# axiom_beta_interface_dummy_v0_13_r1_3.net
KiCad netlist of a schematic drawn in EAGLE
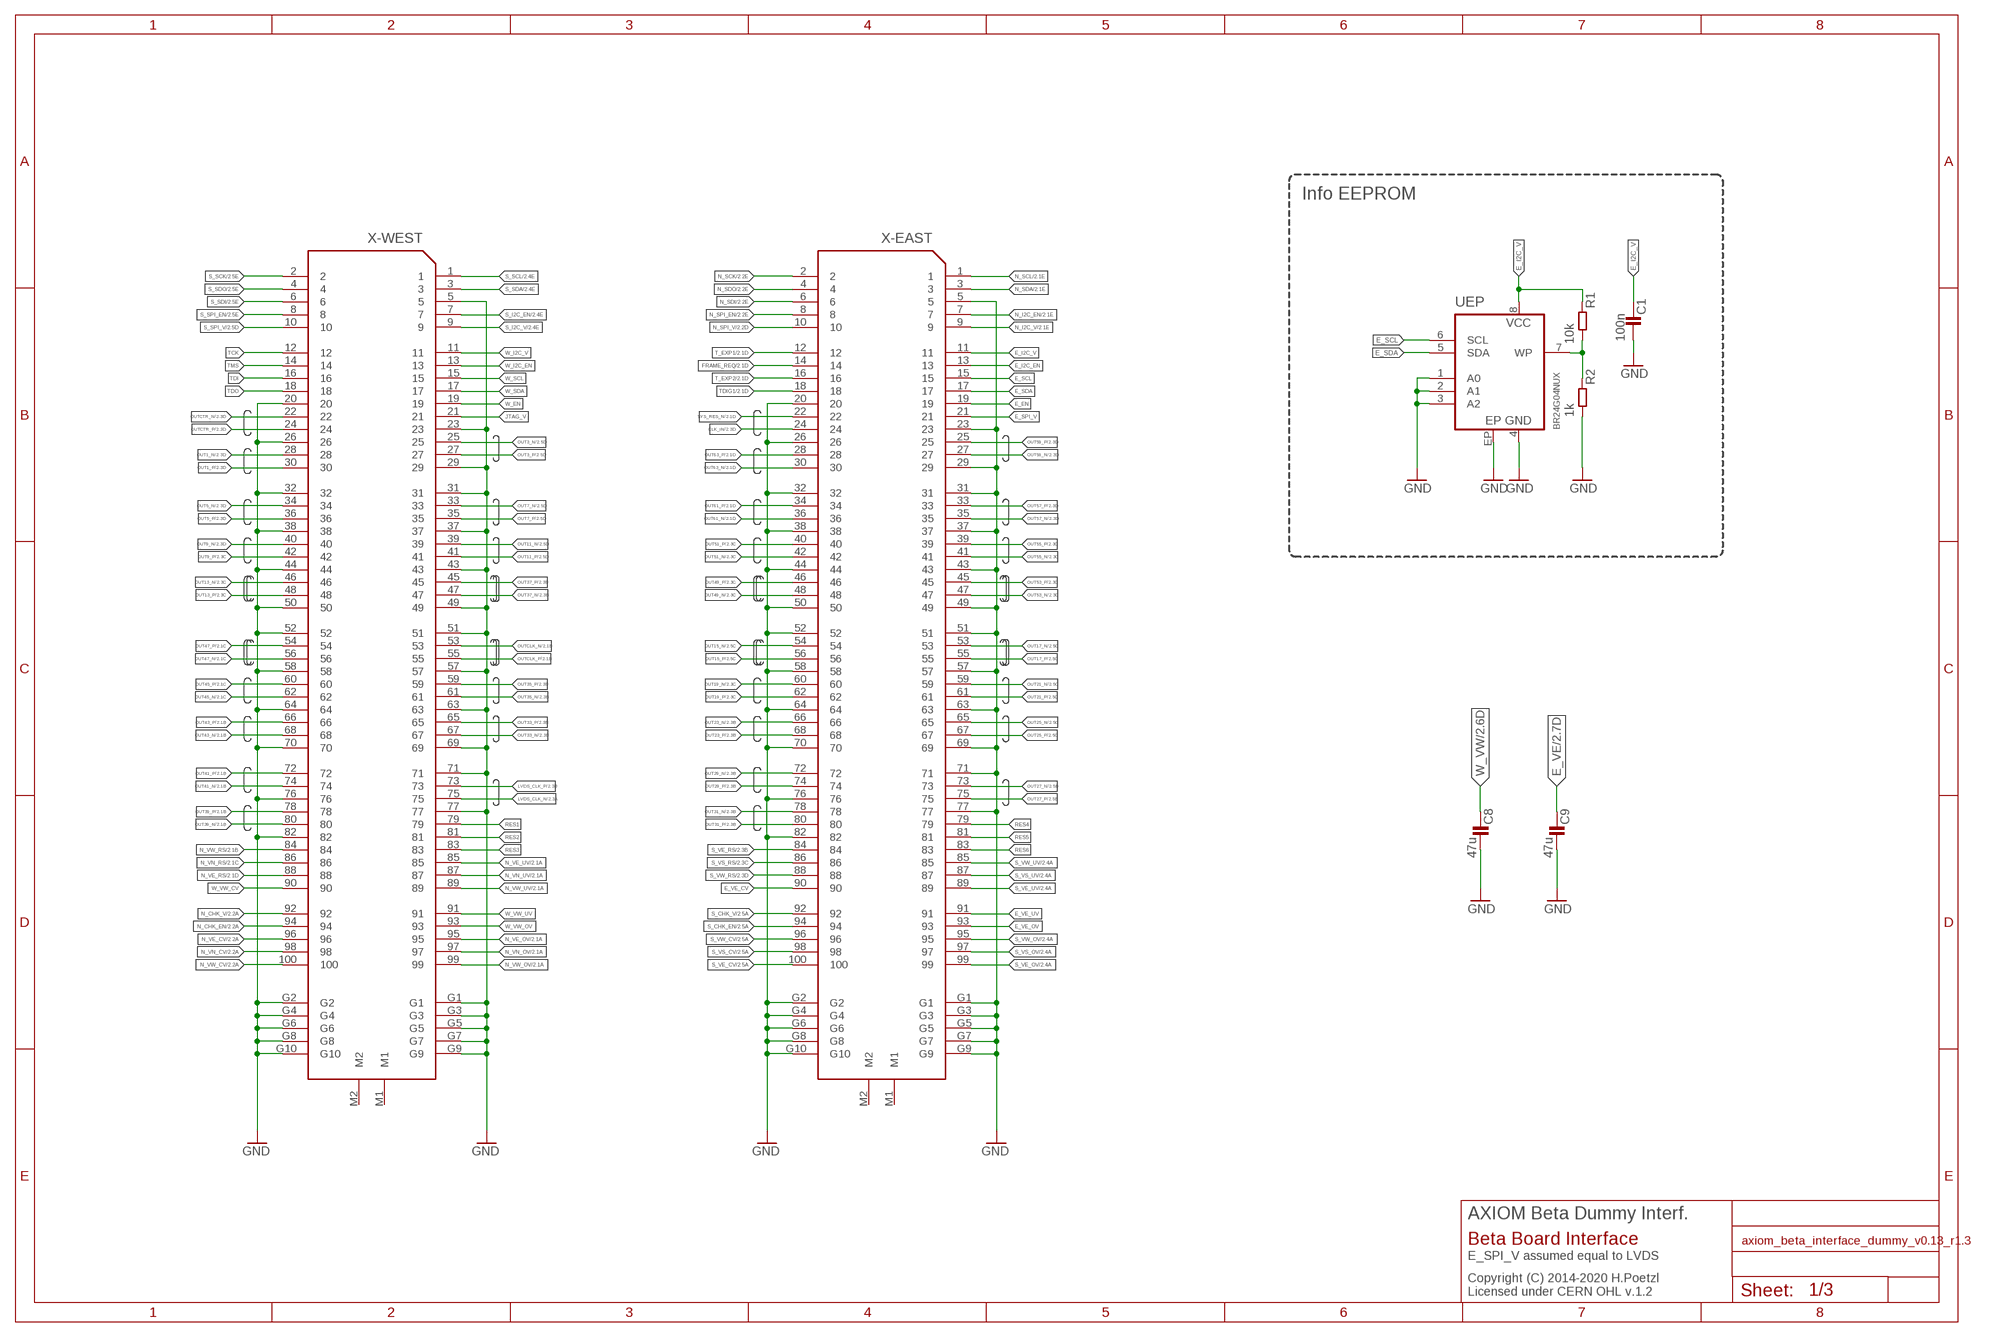
[diagram p0: schematic, sheet 1]
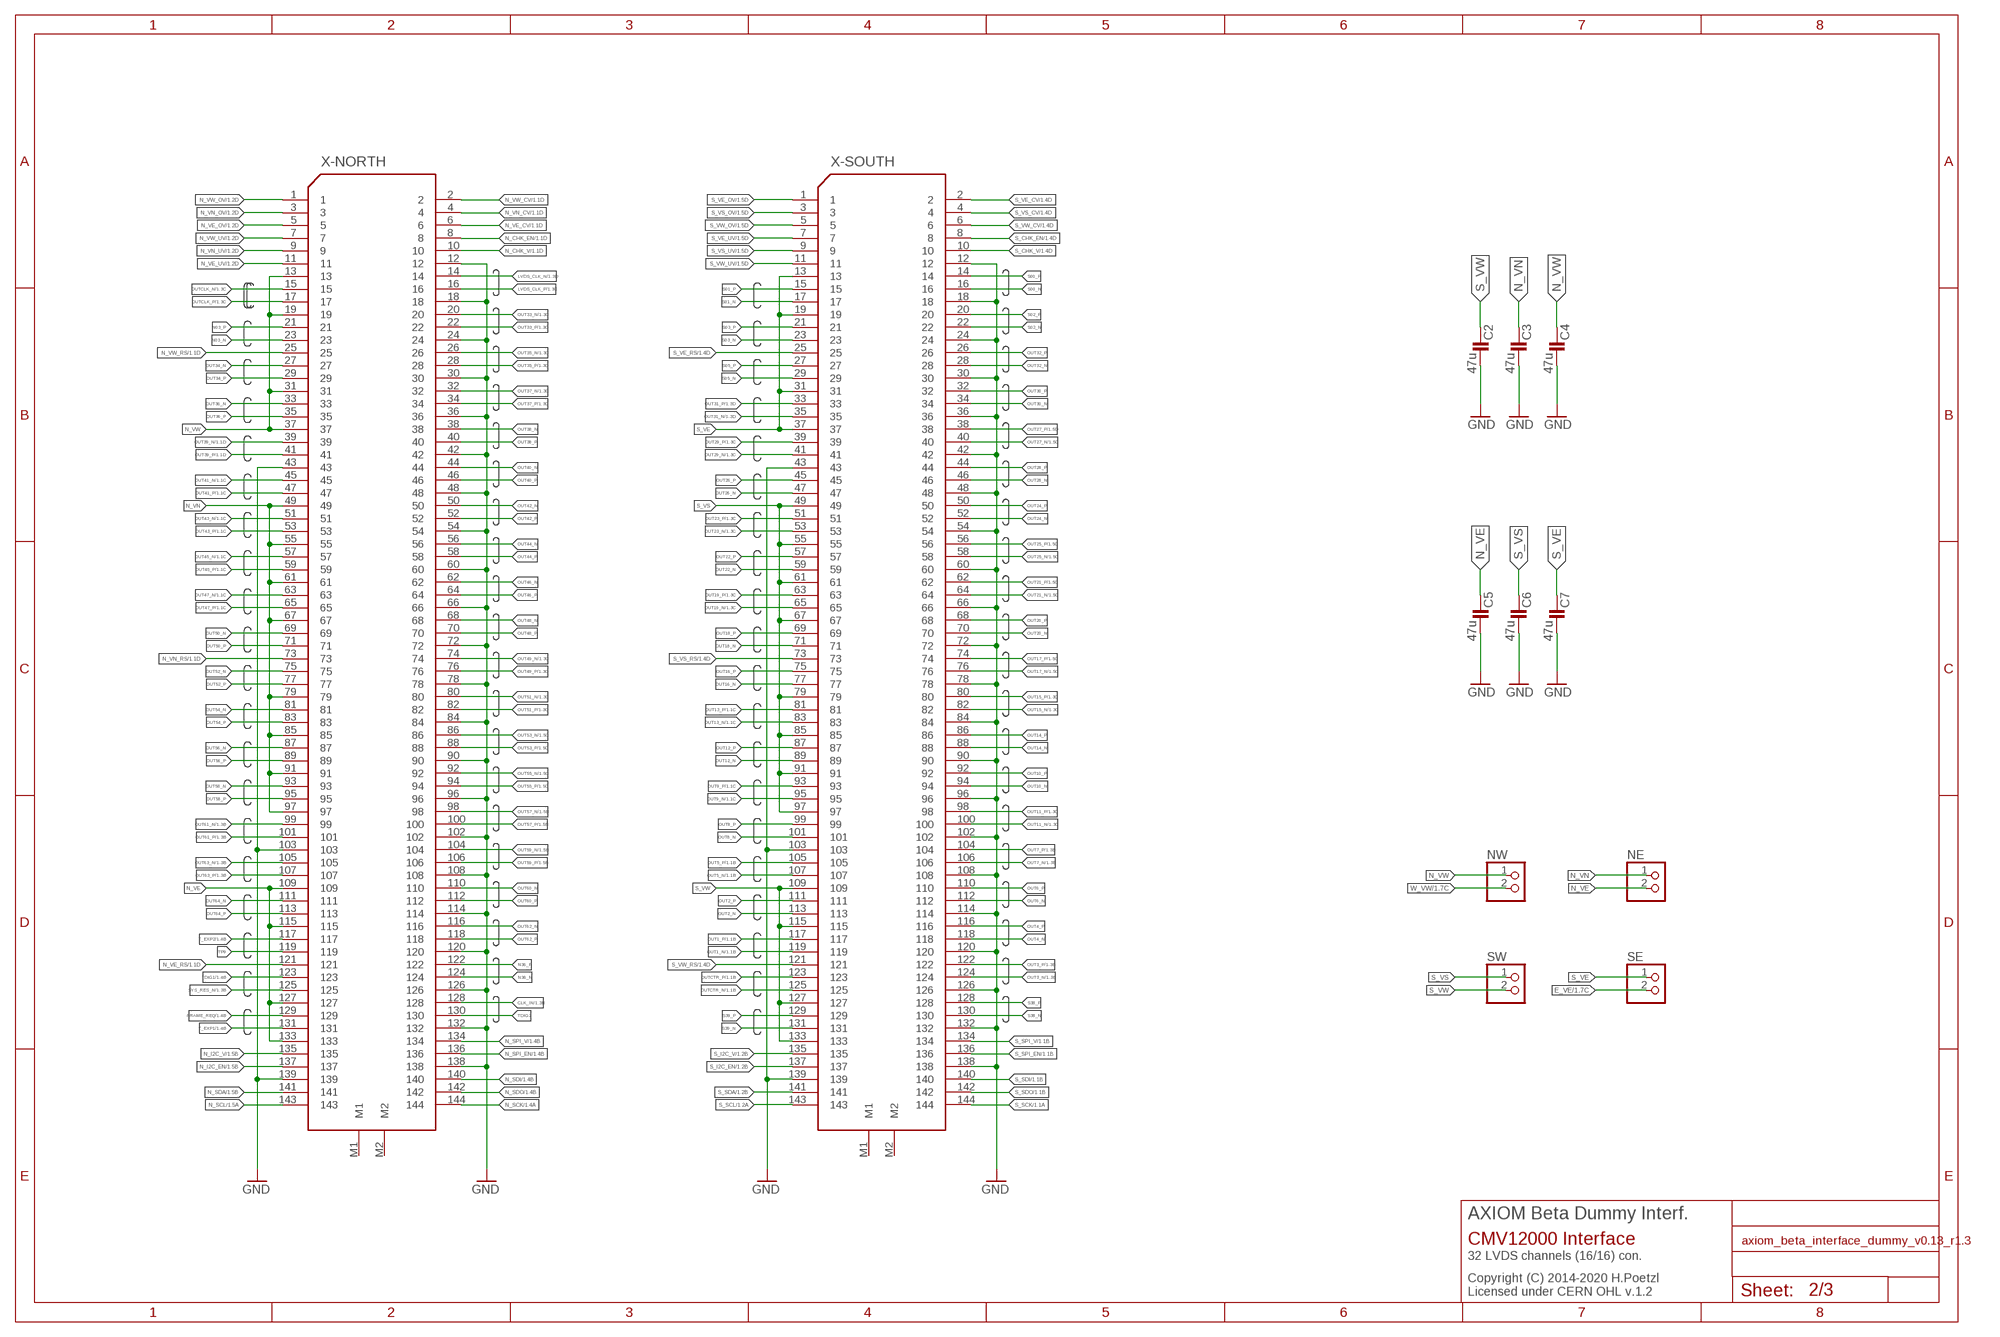
[diagram p1: schematic, sheet 2]
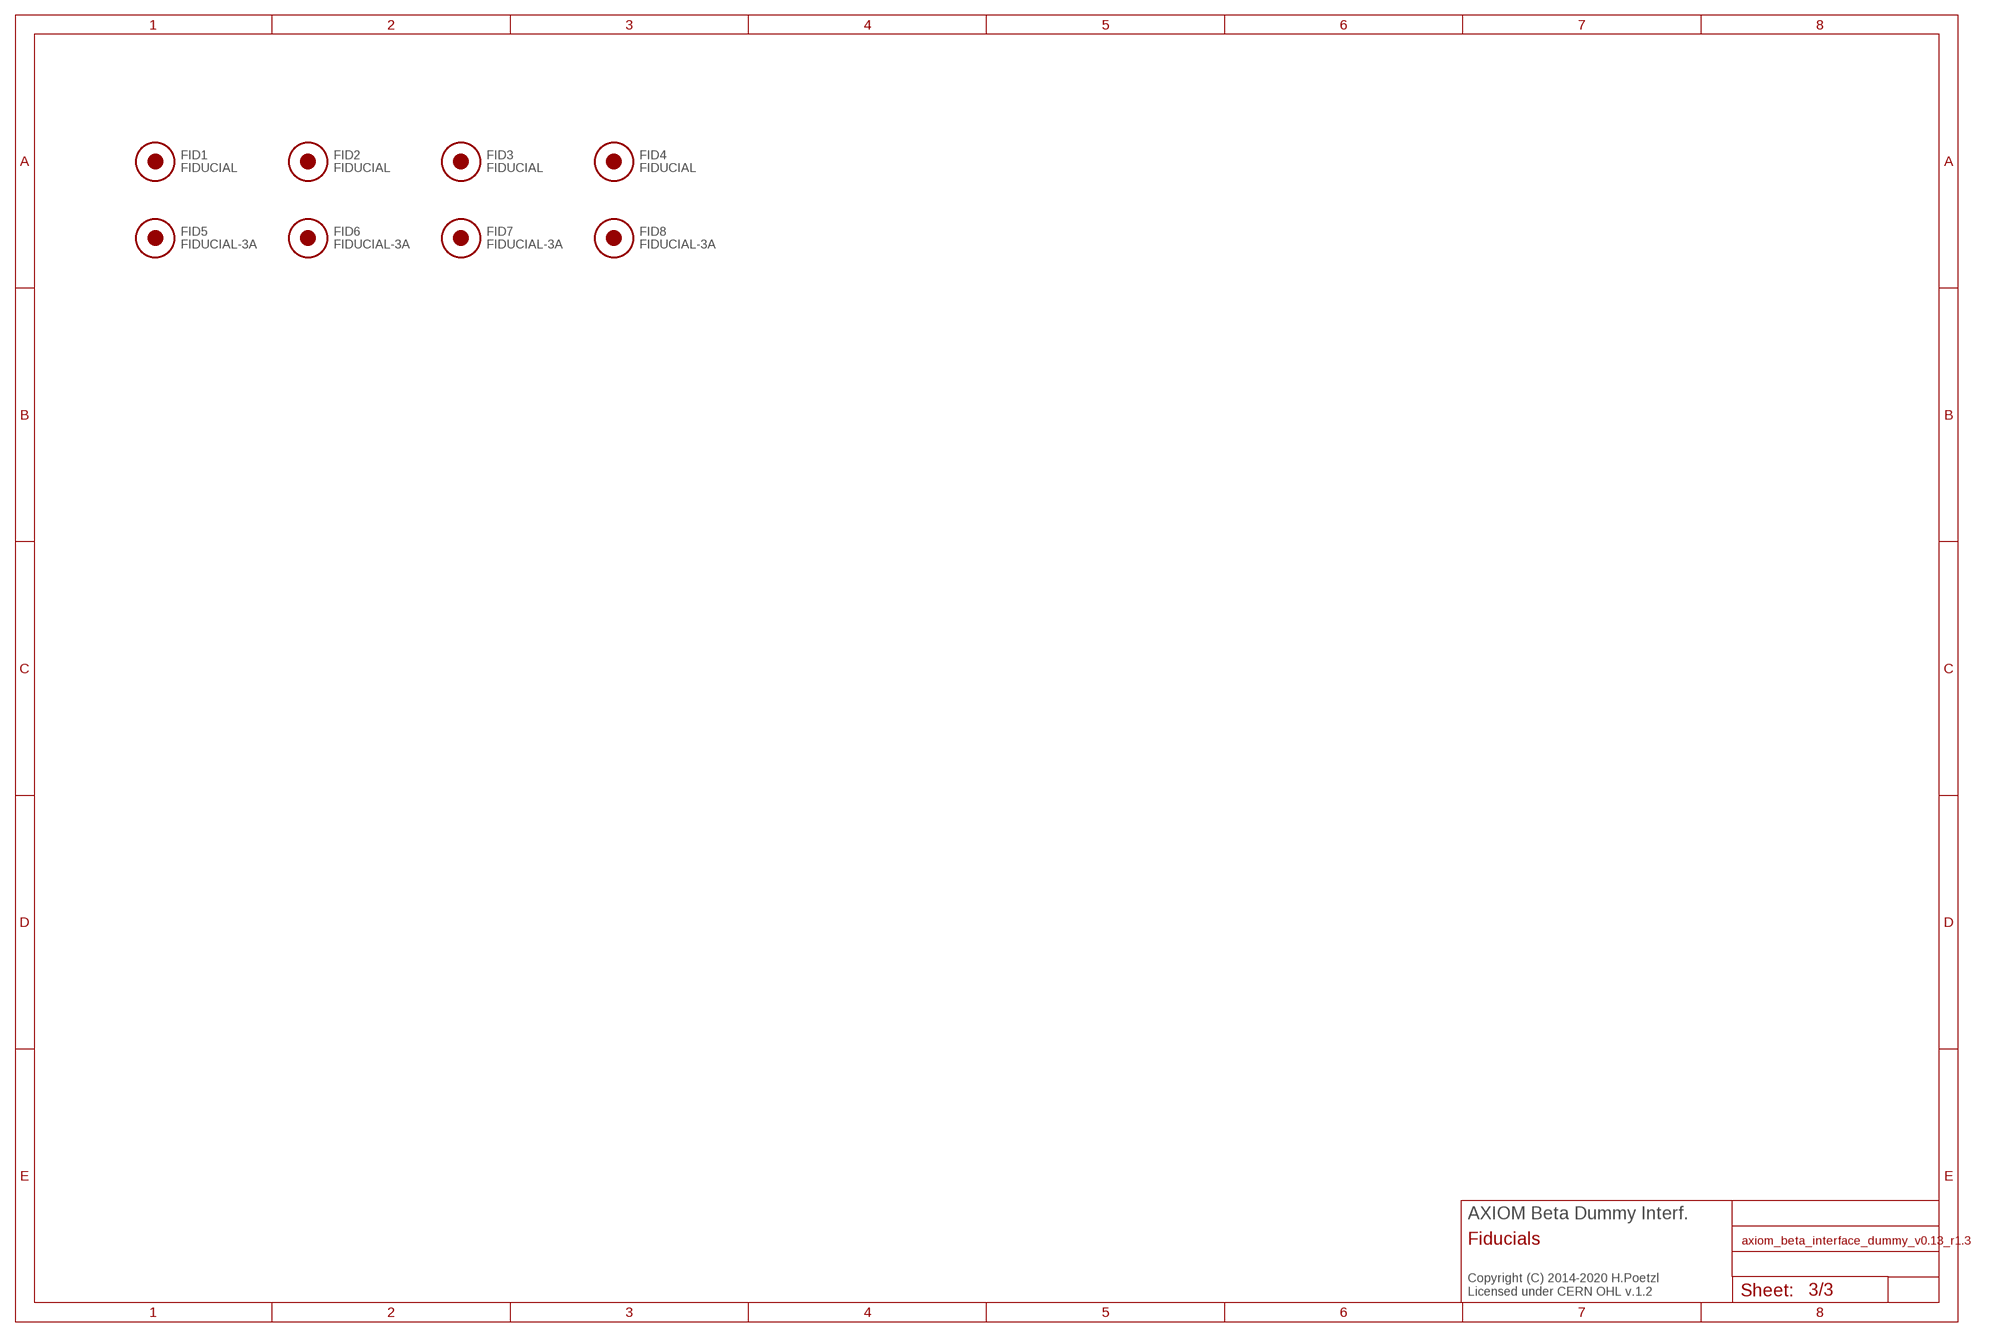
[diagram p2: schematic, sheet 3]

(export (version "E")
  (design (tool "Eeschema 10.0.6"))
  (components
    (comp (ref "C2")
      (value "47u")
      (footprint "eagle-import:0805-B")
      (libsource (lib "eagle-import") (part "C0805-B"))
    )
    (comp (ref "C3")
      (value "47u")
      (footprint "eagle-import:0805-B")
      (libsource (lib "eagle-import") (part "C0805-B"))
    )
    (comp (ref "C4")
      (value "47u")
      (footprint "eagle-import:0805-B")
      (libsource (lib "eagle-import") (part "C0805-B"))
    )
    (comp (ref "C5")
      (value "47u")
      (footprint "eagle-import:0805-B")
      (libsource (lib "eagle-import") (part "C0805-B"))
    )
    (comp (ref "C6")
      (value "47u")
      (footprint "eagle-import:0805-B")
      (libsource (lib "eagle-import") (part "C0805-B"))
    )
    (comp (ref "C7")
      (value "47u")
      (footprint "eagle-import:0805-B")
      (libsource (lib "eagle-import") (part "C0805-B"))
    )
    (comp (ref "NE")
      (value "PINHD-1X02_2.54")
      (footprint "eagle-import:1X02")
      (libsource (lib "eagle-import") (part "PINHD-1X02_2.54"))
    )
    (comp (ref "NW")
      (value "PINHD-1X02_2.54")
      (footprint "eagle-import:1X02")
      (libsource (lib "eagle-import") (part "PINHD-1X02_2.54"))
    )
    (comp (ref "SE")
      (value "PINHD-1X02_2.54")
      (footprint "eagle-import:1X02")
      (libsource (lib "eagle-import") (part "PINHD-1X02_2.54"))
    )
    (comp (ref "SW")
      (value "PINHD-1X02_2.54")
      (footprint "eagle-import:1X02")
      (libsource (lib "eagle-import") (part "PINHD-1X02_2.54"))
    )
    (comp (ref "X-NORTH")
      (value "FX10-144S")
      (footprint "eagle-import:FX10A-144S")
      (libsource (lib "eagle-import") (part "FX10-144S"))
    )
    (comp (ref "X-SOUTH")
      (value "FX10-144S")
      (footprint "eagle-import:FX10A-144S")
      (libsource (lib "eagle-import") (part "FX10-144S"))
    )
    (comp (ref "C1")
      (value "100n")
      (footprint "eagle-import:0402-B")
      (libsource (lib "eagle-import") (part "C0402-B"))
    )
    (comp (ref "C8")
      (value "47u")
      (footprint "eagle-import:0805-B")
      (libsource (lib "eagle-import") (part "C0805-B"))
    )
    (comp (ref "C9")
      (value "47u")
      (footprint "eagle-import:0805-B")
      (libsource (lib "eagle-import") (part "C0805-B"))
    )
    (comp (ref "R1")
      (value "10k")
      (footprint "eagle-import:0402-B")
      (libsource (lib "eagle-import") (part "R0402-B"))
    )
    (comp (ref "R2")
      (value "1k")
      (footprint "eagle-import:0402-B")
      (libsource (lib "eagle-import") (part "R0402-B"))
    )
    (comp (ref "UEP")
      (value "BR24G04NUX")
      (footprint "eagle-import:DFN200X300X100-9N")
      (libsource (lib "eagle-import") (part "BR24G04NUX"))
    )
    (comp (ref "X-EAST")
      (value "FX10-100/10P")
      (footprint "eagle-import:FX10A-100P_10")
      (libsource (lib "eagle-import") (part "FX10-100/10P"))
    )
    (comp (ref "X-WEST")
      (value "FX10-100/10P")
      (footprint "eagle-import:FX10A-100P_10")
      (libsource (lib "eagle-import") (part "FX10-100/10P"))
    )
    (comp (ref "FID1")
      (value "FIDUCIAL")
      (footprint "eagle-import:FID_ARROW")
      (libsource (lib "eagle-import") (part "FIDUCIAL"))
    )
    (comp (ref "FID2")
      (value "FIDUCIAL")
      (footprint "eagle-import:FID_ARROW")
      (libsource (lib "eagle-import") (part "FIDUCIAL"))
    )
    (comp (ref "FID3")
      (value "FIDUCIAL")
      (footprint "eagle-import:FID_ARROW")
      (libsource (lib "eagle-import") (part "FIDUCIAL"))
    )
    (comp (ref "FID4")
      (value "FIDUCIAL")
      (footprint "eagle-import:FID_ARROW")
      (libsource (lib "eagle-import") (part "FIDUCIAL"))
    )
    (comp (ref "FID5")
      (value "FIDUCIAL-3A")
      (footprint "eagle-import:FID_3ARROW")
      (libsource (lib "eagle-import") (part "FIDUCIAL-3A"))
    )
    (comp (ref "FID6")
      (value "FIDUCIAL-3A")
      (footprint "eagle-import:FID_3ARROW")
      (libsource (lib "eagle-import") (part "FIDUCIAL-3A"))
    )
    (comp (ref "FID7")
      (value "FIDUCIAL-3A")
      (footprint "eagle-import:FID_3ARROW")
      (libsource (lib "eagle-import") (part "FIDUCIAL-3A"))
    )
    (comp (ref "FID8")
      (value "FIDUCIAL-3A")
      (footprint "eagle-import:FID_3ARROW")
      (libsource (lib "eagle-import") (part "FIDUCIAL-3A"))
    )
  )
  (nets
    (net (code "1") (name "CLK_IN") (class "Default")
      (node (ref "X-EAST") (pin "24") (pinfunction "24_24") (pintype "bidirectional"))
      (node (ref "X-NORTH") (pin "128") (pinfunction "128_128") (pintype "bidirectional"))
    )
    (net (code "2") (name "E_EN") (class "Default")
      (node (ref "X-EAST") (pin "19") (pinfunction "19_19") (pintype "bidirectional"))
    )
    (net (code "3") (name "E_I2C_EN") (class "Default")
      (node (ref "X-EAST") (pin "13") (pinfunction "13_13") (pintype "bidirectional"))
    )
    (net (code "4") (name "E_I2C_V") (class "Default")
      (node (ref "C1") (pin "1") (pinfunction "1_1") (pintype "passive"))
      (node (ref "R1") (pin "1") (pinfunction "1_1") (pintype "passive"))
      (node (ref "UEP") (pin "8") (pinfunction "VCC_8") (pintype "power_in"))
      (node (ref "X-EAST") (pin "11") (pinfunction "11_11") (pintype "bidirectional"))
    )
    (net (code "5") (name "E_SCL") (class "Default")
      (node (ref "UEP") (pin "6") (pinfunction "SCL_6") (pintype "input"))
      (node (ref "X-EAST") (pin "15") (pinfunction "15_15") (pintype "bidirectional"))
    )
    (net (code "6") (name "E_SDA") (class "Default")
      (node (ref "UEP") (pin "5") (pinfunction "SDA_5") (pintype "bidirectional"))
      (node (ref "X-EAST") (pin "17") (pinfunction "17_17") (pintype "bidirectional"))
    )
    (net (code "7") (name "E_SPI_V") (class "Default")
      (node (ref "X-EAST") (pin "21") (pinfunction "21_21") (pintype "bidirectional"))
    )
    (net (code "8") (name "E_VE") (class "Default")
      (node (ref "C9") (pin "1") (pinfunction "1_1") (pintype "passive"))
      (node (ref "SE") (pin "2") (pinfunction "2_2") (pintype "passive"))
    )
    (net (code "9") (name "E_VE_CV") (class "Default")
      (node (ref "X-EAST") (pin "90") (pinfunction "90_90") (pintype "bidirectional"))
    )
    (net (code "10") (name "E_VE_OV") (class "Default")
      (node (ref "X-EAST") (pin "93") (pinfunction "93_93") (pintype "bidirectional"))
    )
    (net (code "11") (name "E_VE_UV") (class "Default")
      (node (ref "X-EAST") (pin "91") (pinfunction "91_91") (pintype "bidirectional"))
    )
    (net (code "12") (name "FRAME_REQ") (class "Default")
      (node (ref "X-EAST") (pin "14") (pinfunction "14_14") (pintype "bidirectional"))
      (node (ref "X-NORTH") (pin "129") (pinfunction "129_129") (pintype "bidirectional"))
    )
    (net (code "13") (name "GND") (class "Default")
      (node (ref "C1") (pin "2") (pinfunction "2_2") (pintype "passive"))
      (node (ref "C2") (pin "2") (pinfunction "2_2") (pintype "passive"))
      (node (ref "C3") (pin "2") (pinfunction "2_2") (pintype "passive"))
      (node (ref "C4") (pin "2") (pinfunction "2_2") (pintype "passive"))
      (node (ref "C5") (pin "2") (pinfunction "2_2") (pintype "passive"))
      (node (ref "C6") (pin "2") (pinfunction "2_2") (pintype "passive"))
      (node (ref "C7") (pin "2") (pinfunction "2_2") (pintype "passive"))
      (node (ref "C8") (pin "2") (pinfunction "2_2") (pintype "passive"))
      (node (ref "C9") (pin "2") (pinfunction "2_2") (pintype "passive"))
      (node (ref "R2") (pin "2") (pinfunction "2_2") (pintype "passive"))
      (node (ref "UEP") (pin "1") (pinfunction "A0_1") (pintype "input"))
      (node (ref "UEP") (pin "2") (pinfunction "A1_2") (pintype "input"))
      (node (ref "UEP") (pin "3") (pinfunction "A2_3") (pintype "input"))
      (node (ref "UEP") (pin "4") (pinfunction "GND_4") (pintype "passive"))
      (node (ref "UEP") (pin "EP") (pinfunction "EP_EP") (pintype "passive"))
      (node (ref "X-EAST") (pin "20") (pinfunction "20_20") (pintype "bidirectional"))
      (node (ref "X-EAST") (pin "23") (pinfunction "23_23") (pintype "bidirectional"))
      (node (ref "X-EAST") (pin "26") (pinfunction "26_26") (pintype "bidirectional"))
      (node (ref "X-EAST") (pin "29") (pinfunction "29_29") (pintype "bidirectional"))
      (node (ref "X-EAST") (pin "31") (pinfunction "31_31") (pintype "bidirectional"))
      (node (ref "X-EAST") (pin "32") (pinfunction "32_32") (pintype "bidirectional"))
      (node (ref "X-EAST") (pin "37") (pinfunction "37_37") (pintype "bidirectional"))
      (node (ref "X-EAST") (pin "38") (pinfunction "38_38") (pintype "bidirectional"))
      (node (ref "X-EAST") (pin "43") (pinfunction "43_43") (pintype "bidirectional"))
      (node (ref "X-EAST") (pin "44") (pinfunction "44_44") (pintype "bidirectional"))
      (node (ref "X-EAST") (pin "49") (pinfunction "49_49") (pintype "bidirectional"))
      (node (ref "X-EAST") (pin "5") (pinfunction "5_5") (pintype "bidirectional"))
      (node (ref "X-EAST") (pin "50") (pinfunction "50_50") (pintype "bidirectional"))
      (node (ref "X-EAST") (pin "51") (pinfunction "51_51") (pintype "bidirectional"))
      (node (ref "X-EAST") (pin "52") (pinfunction "52_52") (pintype "bidirectional"))
      (node (ref "X-EAST") (pin "57") (pinfunction "57_57") (pintype "bidirectional"))
      (node (ref "X-EAST") (pin "58") (pinfunction "58_58") (pintype "bidirectional"))
      (node (ref "X-EAST") (pin "63") (pinfunction "63_63") (pintype "bidirectional"))
      (node (ref "X-EAST") (pin "64") (pinfunction "64_64") (pintype "bidirectional"))
      (node (ref "X-EAST") (pin "69") (pinfunction "69_69") (pintype "bidirectional"))
      (node (ref "X-EAST") (pin "70") (pinfunction "70_70") (pintype "bidirectional"))
      (node (ref "X-EAST") (pin "71") (pinfunction "71_71") (pintype "bidirectional"))
      (node (ref "X-EAST") (pin "76") (pinfunction "76_76") (pintype "bidirectional"))
      (node (ref "X-EAST") (pin "77") (pinfunction "77_77") (pintype "bidirectional"))
      (node (ref "X-EAST") (pin "82") (pinfunction "82_82") (pintype "bidirectional"))
      (node (ref "X-EAST") (pin "G1") (pinfunction "G1_G1") (pintype "bidirectional"))
      (node (ref "X-EAST") (pin "G10") (pinfunction "G10_G10") (pintype "bidirectional"))
      (node (ref "X-EAST") (pin "G2") (pinfunction "G2_G2") (pintype "bidirectional"))
      (node (ref "X-EAST") (pin "G3") (pinfunction "G3_G3") (pintype "bidirectional"))
      (node (ref "X-EAST") (pin "G4") (pinfunction "G4_G4") (pintype "bidirectional"))
      (node (ref "X-EAST") (pin "G5") (pinfunction "G5_G5") (pintype "bidirectional"))
      (node (ref "X-EAST") (pin "G6") (pinfunction "G6_G6") (pintype "bidirectional"))
      (node (ref "X-EAST") (pin "G7") (pinfunction "G7_G7") (pintype "bidirectional"))
      (node (ref "X-EAST") (pin "G8") (pinfunction "G8_G8") (pintype "bidirectional"))
      (node (ref "X-EAST") (pin "G9") (pinfunction "G9_G9") (pintype "bidirectional"))
      (node (ref "X-NORTH") (pin "102") (pinfunction "102_102") (pintype "bidirectional"))
      (node (ref "X-NORTH") (pin "103") (pinfunction "103_103") (pintype "bidirectional"))
      (node (ref "X-NORTH") (pin "108") (pinfunction "108_108") (pintype "bidirectional"))
      (node (ref "X-NORTH") (pin "114") (pinfunction "114_114") (pintype "bidirectional"))
      (node (ref "X-NORTH") (pin "12") (pinfunction "12_12") (pintype "bidirectional"))
      (node (ref "X-NORTH") (pin "120") (pinfunction "120_120") (pintype "bidirectional"))
      (node (ref "X-NORTH") (pin "126") (pinfunction "126_126") (pintype "bidirectional"))
      (node (ref "X-NORTH") (pin "132") (pinfunction "132_132") (pintype "bidirectional"))
      (node (ref "X-NORTH") (pin "138") (pinfunction "138_138") (pintype "bidirectional"))
      (node (ref "X-NORTH") (pin "139") (pinfunction "139_139") (pintype "bidirectional"))
      (node (ref "X-NORTH") (pin "18") (pinfunction "18_18") (pintype "bidirectional"))
      (node (ref "X-NORTH") (pin "24") (pinfunction "24_24") (pintype "bidirectional"))
      (node (ref "X-NORTH") (pin "30") (pinfunction "30_30") (pintype "bidirectional"))
      (node (ref "X-NORTH") (pin "36") (pinfunction "36_36") (pintype "bidirectional"))
      (node (ref "X-NORTH") (pin "42") (pinfunction "42_42") (pintype "bidirectional"))
      (node (ref "X-NORTH") (pin "43") (pinfunction "43_43") (pintype "bidirectional"))
      (node (ref "X-NORTH") (pin "48") (pinfunction "48_48") (pintype "bidirectional"))
      (node (ref "X-NORTH") (pin "54") (pinfunction "54_54") (pintype "bidirectional"))
      (node (ref "X-NORTH") (pin "60") (pinfunction "60_60") (pintype "bidirectional"))
      (node (ref "X-NORTH") (pin "66") (pinfunction "66_66") (pintype "bidirectional"))
      (node (ref "X-NORTH") (pin "72") (pinfunction "72_72") (pintype "bidirectional"))
      (node (ref "X-NORTH") (pin "78") (pinfunction "78_78") (pintype "bidirectional"))
      (node (ref "X-NORTH") (pin "84") (pinfunction "84_84") (pintype "bidirectional"))
      (node (ref "X-NORTH") (pin "90") (pinfunction "90_90") (pintype "bidirectional"))
      (node (ref "X-NORTH") (pin "96") (pinfunction "96_96") (pintype "bidirectional"))
      (node (ref "X-SOUTH") (pin "102") (pinfunction "102_102") (pintype "bidirectional"))
      (node (ref "X-SOUTH") (pin "103") (pinfunction "103_103") (pintype "bidirectional"))
      (node (ref "X-SOUTH") (pin "108") (pinfunction "108_108") (pintype "bidirectional"))
      (node (ref "X-SOUTH") (pin "114") (pinfunction "114_114") (pintype "bidirectional"))
      (node (ref "X-SOUTH") (pin "12") (pinfunction "12_12") (pintype "bidirectional"))
      (node (ref "X-SOUTH") (pin "120") (pinfunction "120_120") (pintype "bidirectional"))
      (node (ref "X-SOUTH") (pin "126") (pinfunction "126_126") (pintype "bidirectional"))
      (node (ref "X-SOUTH") (pin "132") (pinfunction "132_132") (pintype "bidirectional"))
      (node (ref "X-SOUTH") (pin "138") (pinfunction "138_138") (pintype "bidirectional"))
      (node (ref "X-SOUTH") (pin "139") (pinfunction "139_139") (pintype "bidirectional"))
      (node (ref "X-SOUTH") (pin "18") (pinfunction "18_18") (pintype "bidirectional"))
      (node (ref "X-SOUTH") (pin "24") (pinfunction "24_24") (pintype "bidirectional"))
      (node (ref "X-SOUTH") (pin "30") (pinfunction "30_30") (pintype "bidirectional"))
      (node (ref "X-SOUTH") (pin "36") (pinfunction "36_36") (pintype "bidirectional"))
      (node (ref "X-SOUTH") (pin "42") (pinfunction "42_42") (pintype "bidirectional"))
      (node (ref "X-SOUTH") (pin "43") (pinfunction "43_43") (pintype "bidirectional"))
      (node (ref "X-SOUTH") (pin "48") (pinfunction "48_48") (pintype "bidirectional"))
      (node (ref "X-SOUTH") (pin "54") (pinfunction "54_54") (pintype "bidirectional"))
      (node (ref "X-SOUTH") (pin "60") (pinfunction "60_60") (pintype "bidirectional"))
      (node (ref "X-SOUTH") (pin "66") (pinfunction "66_66") (pintype "bidirectional"))
      (node (ref "X-SOUTH") (pin "72") (pinfunction "72_72") (pintype "bidirectional"))
      (node (ref "X-SOUTH") (pin "78") (pinfunction "78_78") (pintype "bidirectional"))
      (node (ref "X-SOUTH") (pin "84") (pinfunction "84_84") (pintype "bidirectional"))
      (node (ref "X-SOUTH") (pin "90") (pinfunction "90_90") (pintype "bidirectional"))
      (node (ref "X-SOUTH") (pin "96") (pinfunction "96_96") (pintype "bidirectional"))
      (node (ref "X-WEST") (pin "20") (pinfunction "20_20") (pintype "bidirectional"))
      (node (ref "X-WEST") (pin "23") (pinfunction "23_23") (pintype "bidirectional"))
      (node (ref "X-WEST") (pin "26") (pinfunction "26_26") (pintype "bidirectional"))
      (node (ref "X-WEST") (pin "29") (pinfunction "29_29") (pintype "bidirectional"))
      (node (ref "X-WEST") (pin "31") (pinfunction "31_31") (pintype "bidirectional"))
      (node (ref "X-WEST") (pin "32") (pinfunction "32_32") (pintype "bidirectional"))
      (node (ref "X-WEST") (pin "37") (pinfunction "37_37") (pintype "bidirectional"))
      (node (ref "X-WEST") (pin "38") (pinfunction "38_38") (pintype "bidirectional"))
      (node (ref "X-WEST") (pin "43") (pinfunction "43_43") (pintype "bidirectional"))
      (node (ref "X-WEST") (pin "44") (pinfunction "44_44") (pintype "bidirectional"))
      (node (ref "X-WEST") (pin "49") (pinfunction "49_49") (pintype "bidirectional"))
      (node (ref "X-WEST") (pin "5") (pinfunction "5_5") (pintype "bidirectional"))
      (node (ref "X-WEST") (pin "50") (pinfunction "50_50") (pintype "bidirectional"))
      (node (ref "X-WEST") (pin "51") (pinfunction "51_51") (pintype "bidirectional"))
      (node (ref "X-WEST") (pin "52") (pinfunction "52_52") (pintype "bidirectional"))
      (node (ref "X-WEST") (pin "57") (pinfunction "57_57") (pintype "bidirectional"))
      (node (ref "X-WEST") (pin "58") (pinfunction "58_58") (pintype "bidirectional"))
      (node (ref "X-WEST") (pin "63") (pinfunction "63_63") (pintype "bidirectional"))
      (node (ref "X-WEST") (pin "64") (pinfunction "64_64") (pintype "bidirectional"))
      (node (ref "X-WEST") (pin "69") (pinfunction "69_69") (pintype "bidirectional"))
      (node (ref "X-WEST") (pin "70") (pinfunction "70_70") (pintype "bidirectional"))
      (node (ref "X-WEST") (pin "71") (pinfunction "71_71") (pintype "bidirectional"))
      (node (ref "X-WEST") (pin "76") (pinfunction "76_76") (pintype "bidirectional"))
      (node (ref "X-WEST") (pin "77") (pinfunction "77_77") (pintype "bidirectional"))
      (node (ref "X-WEST") (pin "82") (pinfunction "82_82") (pintype "bidirectional"))
      (node (ref "X-WEST") (pin "G1") (pinfunction "G1_G1") (pintype "bidirectional"))
      (node (ref "X-WEST") (pin "G10") (pinfunction "G10_G10") (pintype "bidirectional"))
      (node (ref "X-WEST") (pin "G2") (pinfunction "G2_G2") (pintype "bidirectional"))
      (node (ref "X-WEST") (pin "G3") (pinfunction "G3_G3") (pintype "bidirectional"))
      (node (ref "X-WEST") (pin "G4") (pinfunction "G4_G4") (pintype "bidirectional"))
      (node (ref "X-WEST") (pin "G5") (pinfunction "G5_G5") (pintype "bidirectional"))
      (node (ref "X-WEST") (pin "G6") (pinfunction "G6_G6") (pintype "bidirectional"))
      (node (ref "X-WEST") (pin "G7") (pinfunction "G7_G7") (pintype "bidirectional"))
      (node (ref "X-WEST") (pin "G8") (pinfunction "G8_G8") (pintype "bidirectional"))
      (node (ref "X-WEST") (pin "G9") (pinfunction "G9_G9") (pintype "bidirectional"))
    )
    (net (code "14") (name "JTAG_V") (class "Default")
      (node (ref "X-WEST") (pin "21") (pinfunction "21_21") (pintype "bidirectional"))
    )
    (net (code "15") (name "LVDS_CLK_N") (class "Default")
      (node (ref "X-NORTH") (pin "14") (pinfunction "14_14") (pintype "bidirectional"))
      (node (ref "X-WEST") (pin "75") (pinfunction "75_75") (pintype "bidirectional"))
    )
    (net (code "16") (name "LVDS_CLK_P") (class "Default")
      (node (ref "X-NORTH") (pin "16") (pinfunction "16_16") (pintype "bidirectional"))
      (node (ref "X-WEST") (pin "73") (pinfunction "73_73") (pintype "bidirectional"))
    )
    (net (code "17") (name "N03_N") (class "Default")
      (node (ref "X-NORTH") (pin "23") (pinfunction "23_23") (pintype "bidirectional"))
    )
    (net (code "18") (name "N03_P") (class "Default")
      (node (ref "X-NORTH") (pin "21") (pinfunction "21_21") (pintype "bidirectional"))
    )
    (net (code "19") (name "N36_N") (class "Default")
      (node (ref "X-NORTH") (pin "124") (pinfunction "124_124") (pintype "bidirectional"))
    )
    (net (code "20") (name "N36_P") (class "Default")
      (node (ref "X-NORTH") (pin "122") (pinfunction "122_122") (pintype "bidirectional"))
    )
    (net (code "21") (name "N_CHK_EN") (class "Default")
      (node (ref "X-NORTH") (pin "8") (pinfunction "8_8") (pintype "bidirectional"))
      (node (ref "X-WEST") (pin "94") (pinfunction "94_94") (pintype "bidirectional"))
    )
    (net (code "22") (name "N_CHK_V") (class "Default")
      (node (ref "X-NORTH") (pin "10") (pinfunction "10_10") (pintype "bidirectional"))
      (node (ref "X-WEST") (pin "92") (pinfunction "92_92") (pintype "bidirectional"))
    )
    (net (code "23") (name "N_I2C_EN") (class "Default")
      (node (ref "X-EAST") (pin "7") (pinfunction "7_7") (pintype "bidirectional"))
      (node (ref "X-NORTH") (pin "137") (pinfunction "137_137") (pintype "bidirectional"))
    )
    (net (code "24") (name "N_I2C_V") (class "Default")
      (node (ref "X-EAST") (pin "9") (pinfunction "9_9") (pintype "bidirectional"))
      (node (ref "X-NORTH") (pin "135") (pinfunction "135_135") (pintype "bidirectional"))
    )
    (net (code "25") (name "N_SCK") (class "Default")
      (node (ref "X-EAST") (pin "2") (pinfunction "2_2") (pintype "bidirectional"))
      (node (ref "X-NORTH") (pin "144") (pinfunction "144_144") (pintype "bidirectional"))
    )
    (net (code "26") (name "N_SCL") (class "Default")
      (node (ref "X-EAST") (pin "1") (pinfunction "1_1") (pintype "bidirectional"))
      (node (ref "X-NORTH") (pin "143") (pinfunction "143_143") (pintype "bidirectional"))
    )
    (net (code "27") (name "N_SDA") (class "Default")
      (node (ref "X-EAST") (pin "3") (pinfunction "3_3") (pintype "bidirectional"))
      (node (ref "X-NORTH") (pin "141") (pinfunction "141_141") (pintype "bidirectional"))
    )
    (net (code "28") (name "N_SDI") (class "Default")
      (node (ref "X-EAST") (pin "6") (pinfunction "6_6") (pintype "bidirectional"))
      (node (ref "X-NORTH") (pin "140") (pinfunction "140_140") (pintype "bidirectional"))
    )
    (net (code "29") (name "N_SDO") (class "Default")
      (node (ref "X-EAST") (pin "4") (pinfunction "4_4") (pintype "bidirectional"))
      (node (ref "X-NORTH") (pin "142") (pinfunction "142_142") (pintype "bidirectional"))
    )
    (net (code "30") (name "N_SPI_EN") (class "Default")
      (node (ref "X-EAST") (pin "8") (pinfunction "8_8") (pintype "bidirectional"))
      (node (ref "X-NORTH") (pin "136") (pinfunction "136_136") (pintype "bidirectional"))
    )
    (net (code "31") (name "N_SPI_V") (class "Default")
      (node (ref "X-EAST") (pin "10") (pinfunction "10_10") (pintype "bidirectional"))
      (node (ref "X-NORTH") (pin "134") (pinfunction "134_134") (pintype "bidirectional"))
    )
    (net (code "32") (name "N_VE") (class "Default")
      (node (ref "C5") (pin "1") (pinfunction "1_1") (pintype "passive"))
      (node (ref "NE") (pin "2") (pinfunction "2_2") (pintype "passive"))
      (node (ref "X-NORTH") (pin "109") (pinfunction "109_109") (pintype "bidirectional"))
      (node (ref "X-NORTH") (pin "115") (pinfunction "115_115") (pintype "bidirectional"))
      (node (ref "X-NORTH") (pin "127") (pinfunction "127_127") (pintype "bidirectional"))
      (node (ref "X-NORTH") (pin "133") (pinfunction "133_133") (pintype "bidirectional"))
    )
    (net (code "33") (name "N_VE_CV") (class "Default")
      (node (ref "X-NORTH") (pin "6") (pinfunction "6_6") (pintype "bidirectional"))
      (node (ref "X-WEST") (pin "96") (pinfunction "96_96") (pintype "bidirectional"))
    )
    (net (code "34") (name "N_VE_OV") (class "Default")
      (node (ref "X-NORTH") (pin "5") (pinfunction "5_5") (pintype "bidirectional"))
      (node (ref "X-WEST") (pin "95") (pinfunction "95_95") (pintype "bidirectional"))
    )
    (net (code "35") (name "N_VE_RS") (class "Default")
      (node (ref "X-NORTH") (pin "121") (pinfunction "121_121") (pintype "bidirectional"))
      (node (ref "X-WEST") (pin "88") (pinfunction "88_88") (pintype "bidirectional"))
    )
    (net (code "36") (name "N_VE_UV") (class "Default")
      (node (ref "X-NORTH") (pin "11") (pinfunction "11_11") (pintype "bidirectional"))
      (node (ref "X-WEST") (pin "85") (pinfunction "85_85") (pintype "bidirectional"))
    )
    (net (code "37") (name "N_VN") (class "Default")
      (node (ref "C3") (pin "1") (pinfunction "1_1") (pintype "passive"))
      (node (ref "NE") (pin "1") (pinfunction "1_1") (pintype "passive"))
      (node (ref "X-NORTH") (pin "49") (pinfunction "49_49") (pintype "bidirectional"))
      (node (ref "X-NORTH") (pin "55") (pinfunction "55_55") (pintype "bidirectional"))
      (node (ref "X-NORTH") (pin "61") (pinfunction "61_61") (pintype "bidirectional"))
      (node (ref "X-NORTH") (pin "67") (pinfunction "67_67") (pintype "bidirectional"))
      (node (ref "X-NORTH") (pin "79") (pinfunction "79_79") (pintype "bidirectional"))
      (node (ref "X-NORTH") (pin "85") (pinfunction "85_85") (pintype "bidirectional"))
      (node (ref "X-NORTH") (pin "91") (pinfunction "91_91") (pintype "bidirectional"))
      (node (ref "X-NORTH") (pin "97") (pinfunction "97_97") (pintype "bidirectional"))
    )
    (net (code "38") (name "N_VN_CV") (class "Default")
      (node (ref "X-NORTH") (pin "4") (pinfunction "4_4") (pintype "bidirectional"))
      (node (ref "X-WEST") (pin "98") (pinfunction "98_98") (pintype "bidirectional"))
    )
    (net (code "39") (name "N_VN_OV") (class "Default")
      (node (ref "X-NORTH") (pin "3") (pinfunction "3_3") (pintype "bidirectional"))
      (node (ref "X-WEST") (pin "97") (pinfunction "97_97") (pintype "bidirectional"))
    )
    (net (code "40") (name "N_VN_RS") (class "Default")
      (node (ref "X-NORTH") (pin "73") (pinfunction "73_73") (pintype "bidirectional"))
      (node (ref "X-WEST") (pin "86") (pinfunction "86_86") (pintype "bidirectional"))
    )
    (net (code "41") (name "N_VN_UV") (class "Default")
      (node (ref "X-NORTH") (pin "9") (pinfunction "9_9") (pintype "bidirectional"))
      (node (ref "X-WEST") (pin "87") (pinfunction "87_87") (pintype "bidirectional"))
    )
    (net (code "42") (name "N_VW") (class "Default")
      (node (ref "C4") (pin "1") (pinfunction "1_1") (pintype "passive"))
      (node (ref "NW") (pin "1") (pinfunction "1_1") (pintype "passive"))
      (node (ref "X-NORTH") (pin "13") (pinfunction "13_13") (pintype "bidirectional"))
      (node (ref "X-NORTH") (pin "19") (pinfunction "19_19") (pintype "bidirectional"))
      (node (ref "X-NORTH") (pin "31") (pinfunction "31_31") (pintype "bidirectional"))
      (node (ref "X-NORTH") (pin "37") (pinfunction "37_37") (pintype "bidirectional"))
    )
    (net (code "43") (name "N_VW_CV") (class "Default")
      (node (ref "X-NORTH") (pin "2") (pinfunction "2_2") (pintype "bidirectional"))
      (node (ref "X-WEST") (pin "100") (pinfunction "100_100") (pintype "bidirectional"))
    )
    (net (code "44") (name "N_VW_OV") (class "Default")
      (node (ref "X-NORTH") (pin "1") (pinfunction "1_1") (pintype "bidirectional"))
      (node (ref "X-WEST") (pin "99") (pinfunction "99_99") (pintype "bidirectional"))
    )
    (net (code "45") (name "N_VW_RS") (class "Default")
      (node (ref "X-NORTH") (pin "25") (pinfunction "25_25") (pintype "bidirectional"))
      (node (ref "X-WEST") (pin "84") (pinfunction "84_84") (pintype "bidirectional"))
    )
    (net (code "46") (name "N_VW_UV") (class "Default")
      (node (ref "X-NORTH") (pin "7") (pinfunction "7_7") (pintype "bidirectional"))
      (node (ref "X-WEST") (pin "89") (pinfunction "89_89") (pintype "bidirectional"))
    )
    (net (code "47") (name "Net-(UEP-WP)") (class "Default")
      (node (ref "R1") (pin "2") (pinfunction "2_2") (pintype "passive"))
      (node (ref "R2") (pin "1") (pinfunction "1_1") (pintype "passive"))
      (node (ref "UEP") (pin "7") (pinfunction "WP_7") (pintype "input"))
    )
    (net (code "48") (name "OUT1_N") (class "Default")
      (node (ref "X-SOUTH") (pin "119") (pinfunction "119_119") (pintype "bidirectional"))
      (node (ref "X-WEST") (pin "28") (pinfunction "28_28") (pintype "bidirectional"))
    )
    (net (code "49") (name "OUT1_P") (class "Default")
      (node (ref "X-SOUTH") (pin "117") (pinfunction "117_117") (pintype "bidirectional"))
      (node (ref "X-WEST") (pin "30") (pinfunction "30_30") (pintype "bidirectional"))
    )
    (net (code "50") (name "OUT2_N") (class "Default")
      (node (ref "X-SOUTH") (pin "113") (pinfunction "113_113") (pintype "bidirectional"))
    )
    (net (code "51") (name "OUT2_P") (class "Default")
      (node (ref "X-SOUTH") (pin "111") (pinfunction "111_111") (pintype "bidirectional"))
    )
    (net (code "52") (name "OUT3_N") (class "Default")
      (node (ref "X-SOUTH") (pin "124") (pinfunction "124_124") (pintype "bidirectional"))
      (node (ref "X-WEST") (pin "25") (pinfunction "25_25") (pintype "bidirectional"))
    )
    (net (code "53") (name "OUT3_P") (class "Default")
      (node (ref "X-SOUTH") (pin "122") (pinfunction "122_122") (pintype "bidirectional"))
      (node (ref "X-WEST") (pin "27") (pinfunction "27_27") (pintype "bidirectional"))
    )
    (net (code "54") (name "OUT4_N") (class "Default")
      (node (ref "X-SOUTH") (pin "118") (pinfunction "118_118") (pintype "bidirectional"))
    )
    (net (code "55") (name "OUT4_P") (class "Default")
      (node (ref "X-SOUTH") (pin "116") (pinfunction "116_116") (pintype "bidirectional"))
    )
    (net (code "56") (name "OUT5_N") (class "Default")
      (node (ref "X-SOUTH") (pin "107") (pinfunction "107_107") (pintype "bidirectional"))
      (node (ref "X-WEST") (pin "34") (pinfunction "34_34") (pintype "bidirectional"))
    )
    (net (code "57") (name "OUT5_P") (class "Default")
      (node (ref "X-SOUTH") (pin "105") (pinfunction "105_105") (pintype "bidirectional"))
      (node (ref "X-WEST") (pin "36") (pinfunction "36_36") (pintype "bidirectional"))
    )
    (net (code "58") (name "OUT6_N") (class "Default")
      (node (ref "X-SOUTH") (pin "112") (pinfunction "112_112") (pintype "bidirectional"))
    )
    (net (code "59") (name "OUT6_P") (class "Default")
      (node (ref "X-SOUTH") (pin "110") (pinfunction "110_110") (pintype "bidirectional"))
    )
    (net (code "60") (name "OUT7_N") (class "Default")
      (node (ref "X-SOUTH") (pin "106") (pinfunction "106_106") (pintype "bidirectional"))
      (node (ref "X-WEST") (pin "33") (pinfunction "33_33") (pintype "bidirectional"))
    )
    (net (code "61") (name "OUT7_P") (class "Default")
      (node (ref "X-SOUTH") (pin "104") (pinfunction "104_104") (pintype "bidirectional"))
      (node (ref "X-WEST") (pin "35") (pinfunction "35_35") (pintype "bidirectional"))
    )
    (net (code "62") (name "OUT8_N") (class "Default")
      (node (ref "X-SOUTH") (pin "101") (pinfunction "101_101") (pintype "bidirectional"))
    )
    (net (code "63") (name "OUT8_P") (class "Default")
      (node (ref "X-SOUTH") (pin "99") (pinfunction "99_99") (pintype "bidirectional"))
    )
    (net (code "64") (name "OUT9_N") (class "Default")
      (node (ref "X-SOUTH") (pin "95") (pinfunction "95_95") (pintype "bidirectional"))
      (node (ref "X-WEST") (pin "40") (pinfunction "40_40") (pintype "bidirectional"))
    )
    (net (code "65") (name "OUT9_P") (class "Default")
      (node (ref "X-SOUTH") (pin "93") (pinfunction "93_93") (pintype "bidirectional"))
      (node (ref "X-WEST") (pin "42") (pinfunction "42_42") (pintype "bidirectional"))
    )
    (net (code "66") (name "OUT10_N") (class "Default")
      (node (ref "X-SOUTH") (pin "94") (pinfunction "94_94") (pintype "bidirectional"))
    )
    (net (code "67") (name "OUT10_P") (class "Default")
      (node (ref "X-SOUTH") (pin "92") (pinfunction "92_92") (pintype "bidirectional"))
    )
    (net (code "68") (name "OUT11_N") (class "Default")
      (node (ref "X-SOUTH") (pin "100") (pinfunction "100_100") (pintype "bidirectional"))
      (node (ref "X-WEST") (pin "39") (pinfunction "39_39") (pintype "bidirectional"))
    )
    (net (code "69") (name "OUT11_P") (class "Default")
      (node (ref "X-SOUTH") (pin "98") (pinfunction "98_98") (pintype "bidirectional"))
      (node (ref "X-WEST") (pin "41") (pinfunction "41_41") (pintype "bidirectional"))
    )
    (net (code "70") (name "OUT12_N") (class "Default")
      (node (ref "X-SOUTH") (pin "89") (pinfunction "89_89") (pintype "bidirectional"))
    )
    (net (code "71") (name "OUT12_P") (class "Default")
      (node (ref "X-SOUTH") (pin "87") (pinfunction "87_87") (pintype "bidirectional"))
    )
    (net (code "72") (name "OUT13_N") (class "Default")
      (node (ref "X-SOUTH") (pin "83") (pinfunction "83_83") (pintype "bidirectional"))
      (node (ref "X-WEST") (pin "46") (pinfunction "46_46") (pintype "bidirectional"))
    )
    (net (code "73") (name "OUT13_P") (class "Default")
      (node (ref "X-SOUTH") (pin "81") (pinfunction "81_81") (pintype "bidirectional"))
      (node (ref "X-WEST") (pin "48") (pinfunction "48_48") (pintype "bidirectional"))
    )
    (net (code "74") (name "OUT14_N") (class "Default")
      (node (ref "X-SOUTH") (pin "88") (pinfunction "88_88") (pintype "bidirectional"))
    )
    (net (code "75") (name "OUT14_P") (class "Default")
      (node (ref "X-SOUTH") (pin "86") (pinfunction "86_86") (pintype "bidirectional"))
    )
    (net (code "76") (name "OUT15_N") (class "Default")
      (node (ref "X-EAST") (pin "54") (pinfunction "54_54") (pintype "bidirectional"))
      (node (ref "X-SOUTH") (pin "82") (pinfunction "82_82") (pintype "bidirectional"))
    )
    (net (code "77") (name "OUT15_P") (class "Default")
      (node (ref "X-EAST") (pin "56") (pinfunction "56_56") (pintype "bidirectional"))
      (node (ref "X-SOUTH") (pin "80") (pinfunction "80_80") (pintype "bidirectional"))
    )
    (net (code "78") (name "OUT16_N") (class "Default")
      (node (ref "X-SOUTH") (pin "77") (pinfunction "77_77") (pintype "bidirectional"))
    )
    (net (code "79") (name "OUT16_P") (class "Default")
      (node (ref "X-SOUTH") (pin "75") (pinfunction "75_75") (pintype "bidirectional"))
    )
    (net (code "80") (name "OUT17_N") (class "Default")
      (node (ref "X-EAST") (pin "53") (pinfunction "53_53") (pintype "bidirectional"))
      (node (ref "X-SOUTH") (pin "76") (pinfunction "76_76") (pintype "bidirectional"))
    )
    (net (code "81") (name "OUT17_P") (class "Default")
      (node (ref "X-EAST") (pin "55") (pinfunction "55_55") (pintype "bidirectional"))
      (node (ref "X-SOUTH") (pin "74") (pinfunction "74_74") (pintype "bidirectional"))
    )
    (net (code "82") (name "OUT18_N") (class "Default")
      (node (ref "X-SOUTH") (pin "71") (pinfunction "71_71") (pintype "bidirectional"))
    )
    (net (code "83") (name "OUT18_P") (class "Default")
      (node (ref "X-SOUTH") (pin "69") (pinfunction "69_69") (pintype "bidirectional"))
    )
    (net (code "84") (name "OUT19_N") (class "Default")
      (node (ref "X-EAST") (pin "60") (pinfunction "60_60") (pintype "bidirectional"))
      (node (ref "X-SOUTH") (pin "65") (pinfunction "65_65") (pintype "bidirectional"))
    )
    (net (code "85") (name "OUT19_P") (class "Default")
      (node (ref "X-EAST") (pin "62") (pinfunction "62_62") (pintype "bidirectional"))
      (node (ref "X-SOUTH") (pin "63") (pinfunction "63_63") (pintype "bidirectional"))
    )
    (net (code "86") (name "OUT20_N") (class "Default")
      (node (ref "X-SOUTH") (pin "70") (pinfunction "70_70") (pintype "bidirectional"))
    )
    (net (code "87") (name "OUT20_P") (class "Default")
      (node (ref "X-SOUTH") (pin "68") (pinfunction "68_68") (pintype "bidirectional"))
    )
    (net (code "88") (name "OUT21_N") (class "Default")
      (node (ref "X-EAST") (pin "59") (pinfunction "59_59") (pintype "bidirectional"))
      (node (ref "X-SOUTH") (pin "64") (pinfunction "64_64") (pintype "bidirectional"))
    )
    (net (code "89") (name "OUT21_P") (class "Default")
      (node (ref "X-EAST") (pin "61") (pinfunction "61_61") (pintype "bidirectional"))
      (node (ref "X-SOUTH") (pin "62") (pinfunction "62_62") (pintype "bidirectional"))
    )
    (net (code "90") (name "OUT22_N") (class "Default")
      (node (ref "X-SOUTH") (pin "59") (pinfunction "59_59") (pintype "bidirectional"))
    )
    (net (code "91") (name "OUT22_P") (class "Default")
      (node (ref "X-SOUTH") (pin "57") (pinfunction "57_57") (pintype "bidirectional"))
    )
    (net (code "92") (name "OUT23_N") (class "Default")
      (node (ref "X-EAST") (pin "66") (pinfunction "66_66") (pintype "bidirectional"))
      (node (ref "X-SOUTH") (pin "53") (pinfunction "53_53") (pintype "bidirectional"))
    )
    (net (code "93") (name "OUT23_P") (class "Default")
      (node (ref "X-EAST") (pin "68") (pinfunction "68_68") (pintype "bidirectional"))
      (node (ref "X-SOUTH") (pin "51") (pinfunction "51_51") (pintype "bidirectional"))
    )
    (net (code "94") (name "OUT24_N") (class "Default")
      (node (ref "X-SOUTH") (pin "52") (pinfunction "52_52") (pintype "bidirectional"))
    )
    (net (code "95") (name "OUT24_P") (class "Default")
      (node (ref "X-SOUTH") (pin "50") (pinfunction "50_50") (pintype "bidirectional"))
    )
    (net (code "96") (name "OUT25_N") (class "Default")
      (node (ref "X-EAST") (pin "65") (pinfunction "65_65") (pintype "bidirectional"))
      (node (ref "X-SOUTH") (pin "58") (pinfunction "58_58") (pintype "bidirectional"))
    )
    (net (code "97") (name "OUT25_P") (class "Default")
      (node (ref "X-EAST") (pin "67") (pinfunction "67_67") (pintype "bidirectional"))
      (node (ref "X-SOUTH") (pin "56") (pinfunction "56_56") (pintype "bidirectional"))
    )
    (net (code "98") (name "OUT26_N") (class "Default")
      (node (ref "X-SOUTH") (pin "47") (pinfunction "47_47") (pintype "bidirectional"))
    )
    (net (code "99") (name "OUT26_P") (class "Default")
      (node (ref "X-SOUTH") (pin "45") (pinfunction "45_45") (pintype "bidirectional"))
    )
    (net (code "100") (name "OUT27_N") (class "Default")
      (node (ref "X-EAST") (pin "73") (pinfunction "73_73") (pintype "bidirectional"))
      (node (ref "X-SOUTH") (pin "40") (pinfunction "40_40") (pintype "bidirectional"))
    )
    (net (code "101") (name "OUT27_P") (class "Default")
      (node (ref "X-EAST") (pin "75") (pinfunction "75_75") (pintype "bidirectional"))
      (node (ref "X-SOUTH") (pin "38") (pinfunction "38_38") (pintype "bidirectional"))
    )
    (net (code "102") (name "OUT28_N") (class "Default")
      (node (ref "X-SOUTH") (pin "46") (pinfunction "46_46") (pintype "bidirectional"))
    )
    (net (code "103") (name "OUT28_P") (class "Default")
      (node (ref "X-SOUTH") (pin "44") (pinfunction "44_44") (pintype "bidirectional"))
    )
    (net (code "104") (name "OUT29_N") (class "Default")
      (node (ref "X-EAST") (pin "72") (pinfunction "72_72") (pintype "bidirectional"))
      (node (ref "X-SOUTH") (pin "41") (pinfunction "41_41") (pintype "bidirectional"))
    )
    (net (code "105") (name "OUT29_P") (class "Default")
      (node (ref "X-EAST") (pin "74") (pinfunction "74_74") (pintype "bidirectional"))
      (node (ref "X-SOUTH") (pin "39") (pinfunction "39_39") (pintype "bidirectional"))
    )
    (net (code "106") (name "OUT30_N") (class "Default")
      (node (ref "X-SOUTH") (pin "34") (pinfunction "34_34") (pintype "bidirectional"))
    )
    (net (code "107") (name "OUT30_P") (class "Default")
      (node (ref "X-SOUTH") (pin "32") (pinfunction "32_32") (pintype "bidirectional"))
    )
    (net (code "108") (name "OUT31_N") (class "Default")
      (node (ref "X-EAST") (pin "78") (pinfunction "78_78") (pintype "bidirectional"))
      (node (ref "X-SOUTH") (pin "35") (pinfunction "35_35") (pintype "bidirectional"))
    )
    (net (code "109") (name "OUT31_P") (class "Default")
      (node (ref "X-EAST") (pin "80") (pinfunction "80_80") (pintype "bidirectional"))
      (node (ref "X-SOUTH") (pin "33") (pinfunction "33_33") (pintype "bidirectional"))
    )
    (net (code "110") (name "OUT32_N") (class "Default")
      (node (ref "X-SOUTH") (pin "28") (pinfunction "28_28") (pintype "bidirectional"))
    )
    (net (code "111") (name "OUT32_P") (class "Default")
      (node (ref "X-SOUTH") (pin "26") (pinfunction "26_26") (pintype "bidirectional"))
    )
    (net (code "112") (name "OUT33_N") (class "Default")
      (node (ref "X-NORTH") (pin "20") (pinfunction "20_20") (pintype "bidirectional"))
      (node (ref "X-WEST") (pin "67") (pinfunction "67_67") (pintype "bidirectional"))
    )
    (net (code "113") (name "OUT33_P") (class "Default")
      (node (ref "X-NORTH") (pin "22") (pinfunction "22_22") (pintype "bidirectional"))
      (node (ref "X-WEST") (pin "65") (pinfunction "65_65") (pintype "bidirectional"))
    )
    (net (code "114") (name "OUT34_N") (class "Default")
      (node (ref "X-NORTH") (pin "27") (pinfunction "27_27") (pintype "bidirectional"))
    )
    (net (code "115") (name "OUT34_P") (class "Default")
      (node (ref "X-NORTH") (pin "29") (pinfunction "29_29") (pintype "bidirectional"))
    )
    (net (code "116") (name "OUT35_N") (class "Default")
      (node (ref "X-NORTH") (pin "26") (pinfunction "26_26") (pintype "bidirectional"))
      (node (ref "X-WEST") (pin "61") (pinfunction "61_61") (pintype "bidirectional"))
    )
    (net (code "117") (name "OUT35_P") (class "Default")
      (node (ref "X-NORTH") (pin "28") (pinfunction "28_28") (pintype "bidirectional"))
      (node (ref "X-WEST") (pin "59") (pinfunction "59_59") (pintype "bidirectional"))
    )
    (net (code "118") (name "OUT36_N") (class "Default")
      (node (ref "X-NORTH") (pin "33") (pinfunction "33_33") (pintype "bidirectional"))
    )
    (net (code "119") (name "OUT36_P") (class "Default")
      (node (ref "X-NORTH") (pin "35") (pinfunction "35_35") (pintype "bidirectional"))
    )
    (net (code "120") (name "OUT37_N") (class "Default")
      (node (ref "X-NORTH") (pin "32") (pinfunction "32_32") (pintype "bidirectional"))
      (node (ref "X-WEST") (pin "47") (pinfunction "47_47") (pintype "bidirectional"))
    )
    (net (code "121") (name "OUT37_P") (class "Default")
      (node (ref "X-NORTH") (pin "34") (pinfunction "34_34") (pintype "bidirectional"))
      (node (ref "X-WEST") (pin "45") (pinfunction "45_45") (pintype "bidirectional"))
    )
    (net (code "122") (name "OUT38_N") (class "Default")
      (node (ref "X-NORTH") (pin "38") (pinfunction "38_38") (pintype "bidirectional"))
    )
    (net (code "123") (name "OUT38_P") (class "Default")
      (node (ref "X-NORTH") (pin "40") (pinfunction "40_40") (pintype "bidirectional"))
    )
    (net (code "124") (name "OUT39_N") (class "Default")
      (node (ref "X-NORTH") (pin "39") (pinfunction "39_39") (pintype "bidirectional"))
      (node (ref "X-WEST") (pin "80") (pinfunction "80_80") (pintype "bidirectional"))
    )
    (net (code "125") (name "OUT39_P") (class "Default")
      (node (ref "X-NORTH") (pin "41") (pinfunction "41_41") (pintype "bidirectional"))
      (node (ref "X-WEST") (pin "78") (pinfunction "78_78") (pintype "bidirectional"))
    )
    (net (code "126") (name "OUT40_N") (class "Default")
      (node (ref "X-NORTH") (pin "44") (pinfunction "44_44") (pintype "bidirectional"))
    )
    (net (code "127") (name "OUT40_P") (class "Default")
      (node (ref "X-NORTH") (pin "46") (pinfunction "46_46") (pintype "bidirectional"))
    )
    (net (code "128") (name "OUT41_N") (class "Default")
      (node (ref "X-NORTH") (pin "45") (pinfunction "45_45") (pintype "bidirectional"))
      (node (ref "X-WEST") (pin "74") (pinfunction "74_74") (pintype "bidirectional"))
    )
    (net (code "129") (name "OUT41_P") (class "Default")
      (node (ref "X-NORTH") (pin "47") (pinfunction "47_47") (pintype "bidirectional"))
      (node (ref "X-WEST") (pin "72") (pinfunction "72_72") (pintype "bidirectional"))
    )
    (net (code "130") (name "OUT42_N") (class "Default")
      (node (ref "X-NORTH") (pin "50") (pinfunction "50_50") (pintype "bidirectional"))
    )
    (net (code "131") (name "OUT42_P") (class "Default")
      (node (ref "X-NORTH") (pin "52") (pinfunction "52_52") (pintype "bidirectional"))
    )
    (net (code "132") (name "OUT43_N") (class "Default")
      (node (ref "X-NORTH") (pin "51") (pinfunction "51_51") (pintype "bidirectional"))
      (node (ref "X-WEST") (pin "68") (pinfunction "68_68") (pintype "bidirectional"))
    )
    (net (code "133") (name "OUT43_P") (class "Default")
      (node (ref "X-NORTH") (pin "53") (pinfunction "53_53") (pintype "bidirectional"))
      (node (ref "X-WEST") (pin "66") (pinfunction "66_66") (pintype "bidirectional"))
    )
    (net (code "134") (name "OUT44_N") (class "Default")
      (node (ref "X-NORTH") (pin "56") (pinfunction "56_56") (pintype "bidirectional"))
    )
    (net (code "135") (name "OUT44_P") (class "Default")
      (node (ref "X-NORTH") (pin "58") (pinfunction "58_58") (pintype "bidirectional"))
    )
    (net (code "136") (name "OUT45_N") (class "Default")
      (node (ref "X-NORTH") (pin "57") (pinfunction "57_57") (pintype "bidirectional"))
      (node (ref "X-WEST") (pin "62") (pinfunction "62_62") (pintype "bidirectional"))
    )
    (net (code "137") (name "OUT45_P") (class "Default")
      (node (ref "X-NORTH") (pin "59") (pinfunction "59_59") (pintype "bidirectional"))
      (node (ref "X-WEST") (pin "60") (pinfunction "60_60") (pintype "bidirectional"))
    )
    (net (code "138") (name "OUT46_N") (class "Default")
      (node (ref "X-NORTH") (pin "62") (pinfunction "62_62") (pintype "bidirectional"))
    )
    (net (code "139") (name "OUT46_P") (class "Default")
      (node (ref "X-NORTH") (pin "64") (pinfunction "64_64") (pintype "bidirectional"))
    )
    (net (code "140") (name "OUT47_N") (class "Default")
      (node (ref "X-NORTH") (pin "63") (pinfunction "63_63") (pintype "bidirectional"))
      (node (ref "X-WEST") (pin "56") (pinfunction "56_56") (pintype "bidirectional"))
    )
    (net (code "141") (name "OUT47_P") (class "Default")
      (node (ref "X-NORTH") (pin "65") (pinfunction "65_65") (pintype "bidirectional"))
      (node (ref "X-WEST") (pin "54") (pinfunction "54_54") (pintype "bidirectional"))
    )
    (net (code "142") (name "OUT48_N") (class "Default")
      (node (ref "X-NORTH") (pin "68") (pinfunction "68_68") (pintype "bidirectional"))
    )
    (net (code "143") (name "OUT48_P") (class "Default")
      (node (ref "X-NORTH") (pin "70") (pinfunction "70_70") (pintype "bidirectional"))
    )
    (net (code "144") (name "OUT49_N") (class "Default")
      (node (ref "X-EAST") (pin "48") (pinfunction "48_48") (pintype "bidirectional"))
      (node (ref "X-NORTH") (pin "74") (pinfunction "74_74") (pintype "bidirectional"))
    )
    (net (code "145") (name "OUT49_P") (class "Default")
      (node (ref "X-EAST") (pin "46") (pinfunction "46_46") (pintype "bidirectional"))
      (node (ref "X-NORTH") (pin "76") (pinfunction "76_76") (pintype "bidirectional"))
    )
    (net (code "146") (name "OUT50_N") (class "Default")
      (node (ref "X-NORTH") (pin "69") (pinfunction "69_69") (pintype "bidirectional"))
    )
    (net (code "147") (name "OUT50_P") (class "Default")
      (node (ref "X-NORTH") (pin "71") (pinfunction "71_71") (pintype "bidirectional"))
    )
    (net (code "148") (name "OUT51_N") (class "Default")
      (node (ref "X-EAST") (pin "42") (pinfunction "42_42") (pintype "bidirectional"))
      (node (ref "X-NORTH") (pin "80") (pinfunction "80_80") (pintype "bidirectional"))
    )
    (net (code "149") (name "OUT51_P") (class "Default")
      (node (ref "X-EAST") (pin "40") (pinfunction "40_40") (pintype "bidirectional"))
      (node (ref "X-NORTH") (pin "82") (pinfunction "82_82") (pintype "bidirectional"))
    )
    (net (code "150") (name "OUT52_N") (class "Default")
      (node (ref "X-NORTH") (pin "75") (pinfunction "75_75") (pintype "bidirectional"))
    )
    (net (code "151") (name "OUT52_P") (class "Default")
      (node (ref "X-NORTH") (pin "77") (pinfunction "77_77") (pintype "bidirectional"))
    )
    (net (code "152") (name "OUT53_N") (class "Default")
      (node (ref "X-EAST") (pin "47") (pinfunction "47_47") (pintype "bidirectional"))
      (node (ref "X-NORTH") (pin "86") (pinfunction "86_86") (pintype "bidirectional"))
    )
    (net (code "153") (name "OUT53_P") (class "Default")
      (node (ref "X-EAST") (pin "45") (pinfunction "45_45") (pintype "bidirectional"))
      (node (ref "X-NORTH") (pin "88") (pinfunction "88_88") (pintype "bidirectional"))
    )
    (net (code "154") (name "OUT54_N") (class "Default")
      (node (ref "X-NORTH") (pin "81") (pinfunction "81_81") (pintype "bidirectional"))
    )
    (net (code "155") (name "OUT54_P") (class "Default")
      (node (ref "X-NORTH") (pin "83") (pinfunction "83_83") (pintype "bidirectional"))
    )
    (net (code "156") (name "OUT55_N") (class "Default")
      (node (ref "X-EAST") (pin "41") (pinfunction "41_41") (pintype "bidirectional"))
      (node (ref "X-NORTH") (pin "92") (pinfunction "92_92") (pintype "bidirectional"))
    )
    (net (code "157") (name "OUT55_P") (class "Default")
      (node (ref "X-EAST") (pin "39") (pinfunction "39_39") (pintype "bidirectional"))
      (node (ref "X-NORTH") (pin "94") (pinfunction "94_94") (pintype "bidirectional"))
    )
    (net (code "158") (name "OUT56_N") (class "Default")
      (node (ref "X-NORTH") (pin "87") (pinfunction "87_87") (pintype "bidirectional"))
    )
    (net (code "159") (name "OUT56_P") (class "Default")
      (node (ref "X-NORTH") (pin "89") (pinfunction "89_89") (pintype "bidirectional"))
    )
    (net (code "160") (name "OUT57_N") (class "Default")
      (node (ref "X-EAST") (pin "35") (pinfunction "35_35") (pintype "bidirectional"))
      (node (ref "X-NORTH") (pin "98") (pinfunction "98_98") (pintype "bidirectional"))
    )
    (net (code "161") (name "OUT57_P") (class "Default")
      (node (ref "X-EAST") (pin "33") (pinfunction "33_33") (pintype "bidirectional"))
      (node (ref "X-NORTH") (pin "100") (pinfunction "100_100") (pintype "bidirectional"))
    )
    (net (code "162") (name "OUT58_N") (class "Default")
      (node (ref "X-NORTH") (pin "93") (pinfunction "93_93") (pintype "bidirectional"))
    )
    (net (code "163") (name "OUT58_P") (class "Default")
      (node (ref "X-NORTH") (pin "95") (pinfunction "95_95") (pintype "bidirectional"))
    )
    (net (code "164") (name "OUT59_N") (class "Default")
      (node (ref "X-EAST") (pin "27") (pinfunction "27_27") (pintype "bidirectional"))
      (node (ref "X-NORTH") (pin "104") (pinfunction "104_104") (pintype "bidirectional"))
    )
    (net (code "165") (name "OUT59_P") (class "Default")
      (node (ref "X-EAST") (pin "25") (pinfunction "25_25") (pintype "bidirectional"))
      (node (ref "X-NORTH") (pin "106") (pinfunction "106_106") (pintype "bidirectional"))
    )
    (net (code "166") (name "OUT60_N") (class "Default")
      (node (ref "X-NORTH") (pin "110") (pinfunction "110_110") (pintype "bidirectional"))
    )
    (net (code "167") (name "OUT60_P") (class "Default")
      (node (ref "X-NORTH") (pin "112") (pinfunction "112_112") (pintype "bidirectional"))
    )
    (net (code "168") (name "OUT61_N") (class "Default")
      (node (ref "X-EAST") (pin "36") (pinfunction "36_36") (pintype "bidirectional"))
      (node (ref "X-NORTH") (pin "99") (pinfunction "99_99") (pintype "bidirectional"))
    )
    (net (code "169") (name "OUT61_P") (class "Default")
      (node (ref "X-EAST") (pin "34") (pinfunction "34_34") (pintype "bidirectional"))
      (node (ref "X-NORTH") (pin "101") (pinfunction "101_101") (pintype "bidirectional"))
    )
    (net (code "170") (name "OUT62_N") (class "Default")
      (node (ref "X-NORTH") (pin "116") (pinfunction "116_116") (pintype "bidirectional"))
    )
    (net (code "171") (name "OUT62_P") (class "Default")
      (node (ref "X-NORTH") (pin "118") (pinfunction "118_118") (pintype "bidirectional"))
    )
    (net (code "172") (name "OUT63_N") (class "Default")
      (node (ref "X-EAST") (pin "30") (pinfunction "30_30") (pintype "bidirectional"))
      (node (ref "X-NORTH") (pin "105") (pinfunction "105_105") (pintype "bidirectional"))
    )
    (net (code "173") (name "OUT63_P") (class "Default")
      (node (ref "X-EAST") (pin "28") (pinfunction "28_28") (pintype "bidirectional"))
      (node (ref "X-NORTH") (pin "107") (pinfunction "107_107") (pintype "bidirectional"))
    )
    (net (code "174") (name "OUT64_N") (class "Default")
      (node (ref "X-NORTH") (pin "111") (pinfunction "111_111") (pintype "bidirectional"))
    )
    (net (code "175") (name "OUT64_P") (class "Default")
      (node (ref "X-NORTH") (pin "113") (pinfunction "113_113") (pintype "bidirectional"))
    )
    (net (code "176") (name "OUTCLK_N") (class "Default")
      (node (ref "X-NORTH") (pin "15") (pinfunction "15_15") (pintype "bidirectional"))
      (node (ref "X-WEST") (pin "53") (pinfunction "53_53") (pintype "bidirectional"))
    )
    (net (code "177") (name "OUTCLK_P") (class "Default")
      (node (ref "X-NORTH") (pin "17") (pinfunction "17_17") (pintype "bidirectional"))
      (node (ref "X-WEST") (pin "55") (pinfunction "55_55") (pintype "bidirectional"))
    )
    (net (code "178") (name "OUTCTR_N") (class "Default")
      (node (ref "X-SOUTH") (pin "125") (pinfunction "125_125") (pintype "bidirectional"))
      (node (ref "X-WEST") (pin "22") (pinfunction "22_22") (pintype "bidirectional"))
    )
    (net (code "179") (name "OUTCTR_P") (class "Default")
      (node (ref "X-SOUTH") (pin "123") (pinfunction "123_123") (pintype "bidirectional"))
      (node (ref "X-WEST") (pin "24") (pinfunction "24_24") (pintype "bidirectional"))
    )
    (net (code "180") (name "RES1") (class "Default")
      (node (ref "X-WEST") (pin "79") (pinfunction "79_79") (pintype "bidirectional"))
    )
    (net (code "181") (name "RES2") (class "Default")
      (node (ref "X-WEST") (pin "81") (pinfunction "81_81") (pintype "bidirectional"))
    )
    (net (code "182") (name "RES3") (class "Default")
      (node (ref "X-WEST") (pin "83") (pinfunction "83_83") (pintype "bidirectional"))
    )
    (net (code "183") (name "RES4") (class "Default")
      (node (ref "X-EAST") (pin "79") (pinfunction "79_79") (pintype "bidirectional"))
    )
    (net (code "184") (name "RES5") (class "Default")
      (node (ref "X-EAST") (pin "81") (pinfunction "81_81") (pintype "bidirectional"))
    )
    (net (code "185") (name "RES6") (class "Default")
      (node (ref "X-EAST") (pin "83") (pinfunction "83_83") (pintype "bidirectional"))
    )
    (net (code "186") (name "S00_N") (class "Default")
      (node (ref "X-SOUTH") (pin "16") (pinfunction "16_16") (pintype "bidirectional"))
    )
    (net (code "187") (name "S00_P") (class "Default")
      (node (ref "X-SOUTH") (pin "14") (pinfunction "14_14") (pintype "bidirectional"))
    )
    (net (code "188") (name "S01_N") (class "Default")
      (node (ref "X-SOUTH") (pin "17") (pinfunction "17_17") (pintype "bidirectional"))
    )
    (net (code "189") (name "S01_P") (class "Default")
      (node (ref "X-SOUTH") (pin "15") (pinfunction "15_15") (pintype "bidirectional"))
    )
    (net (code "190") (name "S02_N") (class "Default")
      (node (ref "X-SOUTH") (pin "22") (pinfunction "22_22") (pintype "bidirectional"))
    )
    (net (code "191") (name "S02_P") (class "Default")
      (node (ref "X-SOUTH") (pin "20") (pinfunction "20_20") (pintype "bidirectional"))
    )
    (net (code "192") (name "S03_N") (class "Default")
      (node (ref "X-SOUTH") (pin "23") (pinfunction "23_23") (pintype "bidirectional"))
    )
    (net (code "193") (name "S03_P") (class "Default")
      (node (ref "X-SOUTH") (pin "21") (pinfunction "21_21") (pintype "bidirectional"))
    )
    (net (code "194") (name "S05_N") (class "Default")
      (node (ref "X-SOUTH") (pin "29") (pinfunction "29_29") (pintype "bidirectional"))
    )
    (net (code "195") (name "S05_P") (class "Default")
      (node (ref "X-SOUTH") (pin "27") (pinfunction "27_27") (pintype "bidirectional"))
    )
    (net (code "196") (name "S38_N") (class "Default")
      (node (ref "X-SOUTH") (pin "130") (pinfunction "130_130") (pintype "bidirectional"))
    )
    (net (code "197") (name "S38_P") (class "Default")
      (node (ref "X-SOUTH") (pin "128") (pinfunction "128_128") (pintype "bidirectional"))
    )
    (net (code "198") (name "S39_N") (class "Default")
      (node (ref "X-SOUTH") (pin "131") (pinfunction "131_131") (pintype "bidirectional"))
    )
    (net (code "199") (name "S39_P") (class "Default")
      (node (ref "X-SOUTH") (pin "129") (pinfunction "129_129") (pintype "bidirectional"))
    )
    (net (code "200") (name "SYS_RES_N") (class "Default")
      (node (ref "X-EAST") (pin "22") (pinfunction "22_22") (pintype "bidirectional"))
      (node (ref "X-NORTH") (pin "125") (pinfunction "125_125") (pintype "bidirectional"))
    )
    (net (code "201") (name "S_CHK_EN") (class "Default")
      (node (ref "X-EAST") (pin "94") (pinfunction "94_94") (pintype "bidirectional"))
      (node (ref "X-SOUTH") (pin "8") (pinfunction "8_8") (pintype "bidirectional"))
    )
    (net (code "202") (name "S_CHK_V") (class "Default")
      (node (ref "X-EAST") (pin "92") (pinfunction "92_92") (pintype "bidirectional"))
      (node (ref "X-SOUTH") (pin "10") (pinfunction "10_10") (pintype "bidirectional"))
    )
    (net (code "203") (name "S_I2C_EN") (class "Default")
      (node (ref "X-SOUTH") (pin "137") (pinfunction "137_137") (pintype "bidirectional"))
      (node (ref "X-WEST") (pin "7") (pinfunction "7_7") (pintype "bidirectional"))
    )
    (net (code "204") (name "S_I2C_V") (class "Default")
      (node (ref "X-SOUTH") (pin "135") (pinfunction "135_135") (pintype "bidirectional"))
      (node (ref "X-WEST") (pin "9") (pinfunction "9_9") (pintype "bidirectional"))
    )
    (net (code "205") (name "S_SCK") (class "Default")
      (node (ref "X-SOUTH") (pin "144") (pinfunction "144_144") (pintype "bidirectional"))
      (node (ref "X-WEST") (pin "2") (pinfunction "2_2") (pintype "bidirectional"))
    )
    (net (code "206") (name "S_SCL") (class "Default")
      (node (ref "X-SOUTH") (pin "143") (pinfunction "143_143") (pintype "bidirectional"))
      (node (ref "X-WEST") (pin "1") (pinfunction "1_1") (pintype "bidirectional"))
    )
    (net (code "207") (name "S_SDA") (class "Default")
      (node (ref "X-SOUTH") (pin "141") (pinfunction "141_141") (pintype "bidirectional"))
      (node (ref "X-WEST") (pin "3") (pinfunction "3_3") (pintype "bidirectional"))
    )
    (net (code "208") (name "S_SDI") (class "Default")
      (node (ref "X-SOUTH") (pin "140") (pinfunction "140_140") (pintype "bidirectional"))
      (node (ref "X-WEST") (pin "6") (pinfunction "6_6") (pintype "bidirectional"))
    )
    (net (code "209") (name "S_SDO") (class "Default")
      (node (ref "X-SOUTH") (pin "142") (pinfunction "142_142") (pintype "bidirectional"))
      (node (ref "X-WEST") (pin "4") (pinfunction "4_4") (pintype "bidirectional"))
    )
    (net (code "210") (name "S_SPI_EN") (class "Default")
      (node (ref "X-SOUTH") (pin "136") (pinfunction "136_136") (pintype "bidirectional"))
      (node (ref "X-WEST") (pin "8") (pinfunction "8_8") (pintype "bidirectional"))
    )
    (net (code "211") (name "S_SPI_V") (class "Default")
      (node (ref "X-SOUTH") (pin "134") (pinfunction "134_134") (pintype "bidirectional"))
      (node (ref "X-WEST") (pin "10") (pinfunction "10_10") (pintype "bidirectional"))
    )
    (net (code "212") (name "S_VE") (class "Default")
      (node (ref "C7") (pin "1") (pinfunction "1_1") (pintype "passive"))
      (node (ref "SE") (pin "1") (pinfunction "1_1") (pintype "passive"))
      (node (ref "X-SOUTH") (pin "13") (pinfunction "13_13") (pintype "bidirectional"))
      (node (ref "X-SOUTH") (pin "19") (pinfunction "19_19") (pintype "bidirectional"))
      (node (ref "X-SOUTH") (pin "31") (pinfunction "31_31") (pintype "bidirectional"))
      (node (ref "X-SOUTH") (pin "37") (pinfunction "37_37") (pintype "bidirectional"))
    )
    (net (code "213") (name "S_VE_CV") (class "Default")
      (node (ref "X-EAST") (pin "100") (pinfunction "100_100") (pintype "bidirectional"))
      (node (ref "X-SOUTH") (pin "2") (pinfunction "2_2") (pintype "bidirectional"))
    )
    (net (code "214") (name "S_VE_OV") (class "Default")
      (node (ref "X-EAST") (pin "99") (pinfunction "99_99") (pintype "bidirectional"))
      (node (ref "X-SOUTH") (pin "1") (pinfunction "1_1") (pintype "bidirectional"))
    )
    (net (code "215") (name "S_VE_RS") (class "Default")
      (node (ref "X-EAST") (pin "84") (pinfunction "84_84") (pintype "bidirectional"))
      (node (ref "X-SOUTH") (pin "25") (pinfunction "25_25") (pintype "bidirectional"))
    )
    (net (code "216") (name "S_VE_UV") (class "Default")
      (node (ref "X-EAST") (pin "89") (pinfunction "89_89") (pintype "bidirectional"))
      (node (ref "X-SOUTH") (pin "7") (pinfunction "7_7") (pintype "bidirectional"))
    )
    (net (code "217") (name "S_VS") (class "Default")
      (node (ref "C6") (pin "1") (pinfunction "1_1") (pintype "passive"))
      (node (ref "SW") (pin "1") (pinfunction "1_1") (pintype "passive"))
      (node (ref "X-SOUTH") (pin "49") (pinfunction "49_49") (pintype "bidirectional"))
      (node (ref "X-SOUTH") (pin "55") (pinfunction "55_55") (pintype "bidirectional"))
      (node (ref "X-SOUTH") (pin "61") (pinfunction "61_61") (pintype "bidirectional"))
      (node (ref "X-SOUTH") (pin "67") (pinfunction "67_67") (pintype "bidirectional"))
      (node (ref "X-SOUTH") (pin "79") (pinfunction "79_79") (pintype "bidirectional"))
      (node (ref "X-SOUTH") (pin "85") (pinfunction "85_85") (pintype "bidirectional"))
      (node (ref "X-SOUTH") (pin "91") (pinfunction "91_91") (pintype "bidirectional"))
      (node (ref "X-SOUTH") (pin "97") (pinfunction "97_97") (pintype "bidirectional"))
    )
    (net (code "218") (name "S_VS_CV") (class "Default")
      (node (ref "X-EAST") (pin "98") (pinfunction "98_98") (pintype "bidirectional"))
      (node (ref "X-SOUTH") (pin "4") (pinfunction "4_4") (pintype "bidirectional"))
    )
    (net (code "219") (name "S_VS_OV") (class "Default")
      (node (ref "X-EAST") (pin "97") (pinfunction "97_97") (pintype "bidirectional"))
      (node (ref "X-SOUTH") (pin "3") (pinfunction "3_3") (pintype "bidirectional"))
    )
    (net (code "220") (name "S_VS_RS") (class "Default")
      (node (ref "X-EAST") (pin "86") (pinfunction "86_86") (pintype "bidirectional"))
      (node (ref "X-SOUTH") (pin "73") (pinfunction "73_73") (pintype "bidirectional"))
    )
    (net (code "221") (name "S_VS_UV") (class "Default")
      (node (ref "X-EAST") (pin "87") (pinfunction "87_87") (pintype "bidirectional"))
      (node (ref "X-SOUTH") (pin "9") (pinfunction "9_9") (pintype "bidirectional"))
    )
    (net (code "222") (name "S_VW") (class "Default")
      (node (ref "C2") (pin "1") (pinfunction "1_1") (pintype "passive"))
      (node (ref "SW") (pin "2") (pinfunction "2_2") (pintype "passive"))
      (node (ref "X-SOUTH") (pin "109") (pinfunction "109_109") (pintype "bidirectional"))
      (node (ref "X-SOUTH") (pin "115") (pinfunction "115_115") (pintype "bidirectional"))
      (node (ref "X-SOUTH") (pin "127") (pinfunction "127_127") (pintype "bidirectional"))
      (node (ref "X-SOUTH") (pin "133") (pinfunction "133_133") (pintype "bidirectional"))
    )
    (net (code "223") (name "S_VW_CV") (class "Default")
      (node (ref "X-EAST") (pin "96") (pinfunction "96_96") (pintype "bidirectional"))
      (node (ref "X-SOUTH") (pin "6") (pinfunction "6_6") (pintype "bidirectional"))
    )
    (net (code "224") (name "S_VW_OV") (class "Default")
      (node (ref "X-EAST") (pin "95") (pinfunction "95_95") (pintype "bidirectional"))
      (node (ref "X-SOUTH") (pin "5") (pinfunction "5_5") (pintype "bidirectional"))
    )
    (net (code "225") (name "S_VW_RS") (class "Default")
      (node (ref "X-EAST") (pin "88") (pinfunction "88_88") (pintype "bidirectional"))
      (node (ref "X-SOUTH") (pin "121") (pinfunction "121_121") (pintype "bidirectional"))
    )
    (net (code "226") (name "S_VW_UV") (class "Default")
      (node (ref "X-EAST") (pin "85") (pinfunction "85_85") (pintype "bidirectional"))
      (node (ref "X-SOUTH") (pin "11") (pinfunction "11_11") (pintype "bidirectional"))
    )
    (net (code "227") (name "TCK") (class "Default")
      (node (ref "X-WEST") (pin "12") (pinfunction "12_12") (pintype "bidirectional"))
    )
    (net (code "228") (name "TDI") (class "Default")
      (node (ref "X-WEST") (pin "16") (pinfunction "16_16") (pintype "bidirectional"))
    )
    (net (code "229") (name "TDIG1") (class "Default")
      (node (ref "X-EAST") (pin "18") (pinfunction "18_18") (pintype "bidirectional"))
      (node (ref "X-NORTH") (pin "123") (pinfunction "123_123") (pintype "bidirectional"))
    )
    (net (code "230") (name "TDIG2") (class "Default")
      (node (ref "X-NORTH") (pin "130") (pinfunction "130_130") (pintype "bidirectional"))
    )
    (net (code "231") (name "TDO") (class "Default")
      (node (ref "X-WEST") (pin "18") (pinfunction "18_18") (pintype "bidirectional"))
    )
    (net (code "232") (name "TMS") (class "Default")
      (node (ref "X-WEST") (pin "14") (pinfunction "14_14") (pintype "bidirectional"))
    )
    (net (code "233") (name "TP9") (class "Default")
      (node (ref "X-NORTH") (pin "119") (pinfunction "119_119") (pintype "bidirectional"))
    )
    (net (code "234") (name "T_EXP1") (class "Default")
      (node (ref "X-EAST") (pin "12") (pinfunction "12_12") (pintype "bidirectional"))
      (node (ref "X-NORTH") (pin "131") (pinfunction "131_131") (pintype "bidirectional"))
    )
    (net (code "235") (name "T_EXP2") (class "Default")
      (node (ref "X-EAST") (pin "16") (pinfunction "16_16") (pintype "bidirectional"))
      (node (ref "X-NORTH") (pin "117") (pinfunction "117_117") (pintype "bidirectional"))
    )
    (net (code "236") (name "W_EN") (class "Default")
      (node (ref "X-WEST") (pin "19") (pinfunction "19_19") (pintype "bidirectional"))
    )
    (net (code "237") (name "W_I2C_EN") (class "Default")
      (node (ref "X-WEST") (pin "13") (pinfunction "13_13") (pintype "bidirectional"))
    )
    (net (code "238") (name "W_I2C_V") (class "Default")
      (node (ref "X-WEST") (pin "11") (pinfunction "11_11") (pintype "bidirectional"))
    )
    (net (code "239") (name "W_SCL") (class "Default")
      (node (ref "X-WEST") (pin "15") (pinfunction "15_15") (pintype "bidirectional"))
    )
    (net (code "240") (name "W_SDA") (class "Default")
      (node (ref "X-WEST") (pin "17") (pinfunction "17_17") (pintype "bidirectional"))
    )
    (net (code "241") (name "W_VW") (class "Default")
      (node (ref "C8") (pin "1") (pinfunction "1_1") (pintype "passive"))
      (node (ref "NW") (pin "2") (pinfunction "2_2") (pintype "passive"))
    )
    (net (code "242") (name "W_VW_CV") (class "Default")
      (node (ref "X-WEST") (pin "90") (pinfunction "90_90") (pintype "bidirectional"))
    )
    (net (code "243") (name "W_VW_OV") (class "Default")
      (node (ref "X-WEST") (pin "93") (pinfunction "93_93") (pintype "bidirectional"))
    )
    (net (code "244") (name "W_VW_UV") (class "Default")
      (node (ref "X-WEST") (pin "91") (pinfunction "91_91") (pintype "bidirectional"))
    )
    (net (code "245") (name "unconnected-(X-EAST-PadM1)") (class "Default")
      (node (ref "X-EAST") (pin "M1") (pinfunction "M1_M1") (pintype "bidirectional"))
    )
    (net (code "246") (name "unconnected-(X-EAST-PadM2)") (class "Default")
      (node (ref "X-EAST") (pin "M2") (pinfunction "M2_M2") (pintype "bidirectional"))
    )
    (net (code "247") (name "unconnected-(X-NORTH-PadM1)") (class "Default")
      (node (ref "X-NORTH") (pin "M1") (pinfunction "M1_M1") (pintype "bidirectional"))
    )
    (net (code "248") (name "unconnected-(X-NORTH-PadM2)") (class "Default")
      (node (ref "X-NORTH") (pin "M2") (pinfunction "M2_M2") (pintype "bidirectional"))
    )
    (net (code "249") (name "unconnected-(X-SOUTH-PadM1)") (class "Default")
      (node (ref "X-SOUTH") (pin "M1") (pinfunction "M1_M1") (pintype "bidirectional"))
    )
    (net (code "250") (name "unconnected-(X-SOUTH-PadM2)") (class "Default")
      (node (ref "X-SOUTH") (pin "M2") (pinfunction "M2_M2") (pintype "bidirectional"))
    )
    (net (code "251") (name "unconnected-(X-WEST-PadM1)") (class "Default")
      (node (ref "X-WEST") (pin "M1") (pinfunction "M1_M1") (pintype "bidirectional"))
    )
    (net (code "252") (name "unconnected-(X-WEST-PadM2)") (class "Default")
      (node (ref "X-WEST") (pin "M2") (pinfunction "M2_M2") (pintype "bidirectional"))
    )
  )
)
